# MAAV_Vehicle_12v0.net
KiCad netlist of a schematic drawn in EAGLE
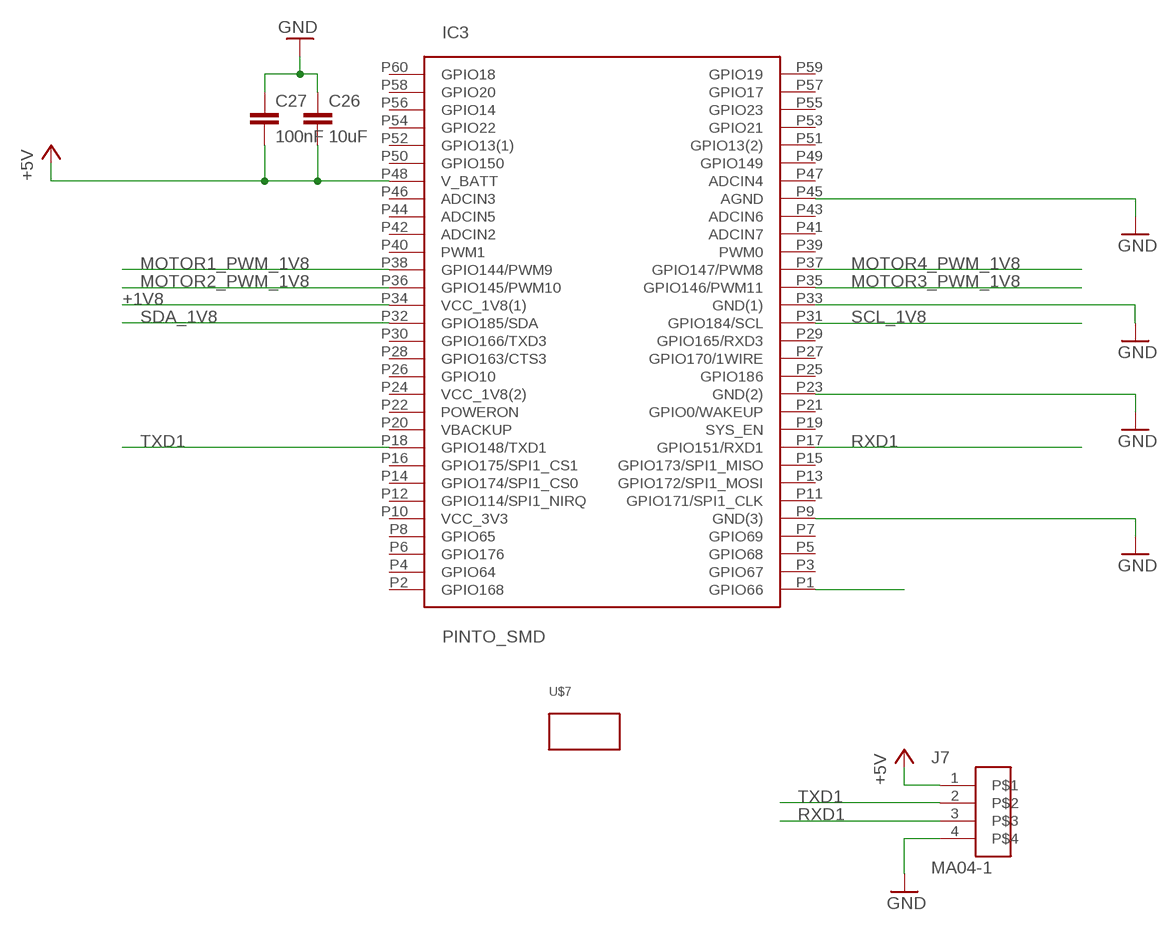
[diagram p0: schematic, sheet 1]
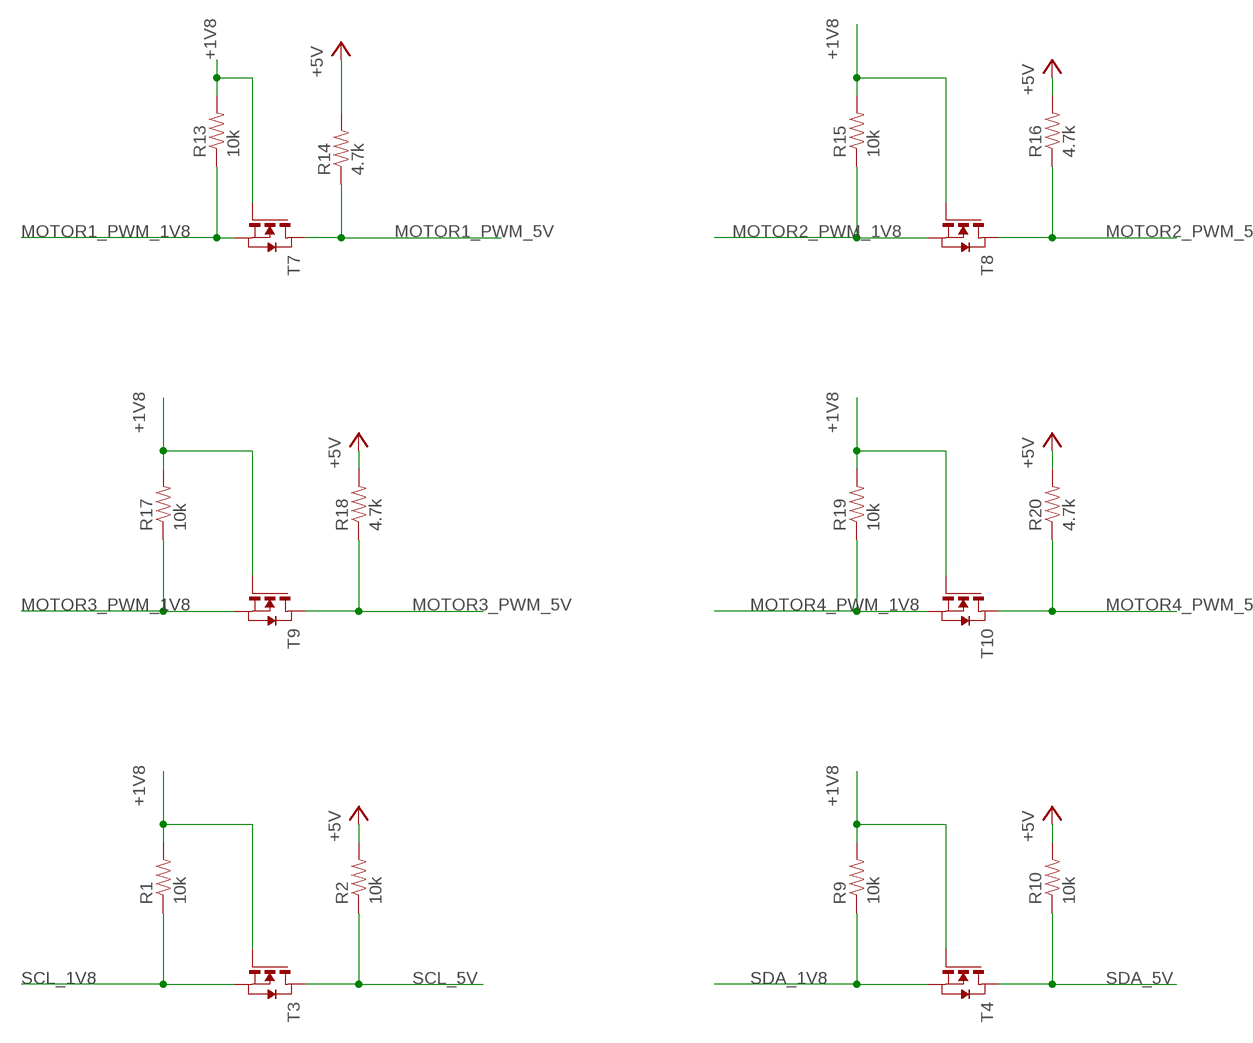
[diagram p1: schematic, sheet 2]
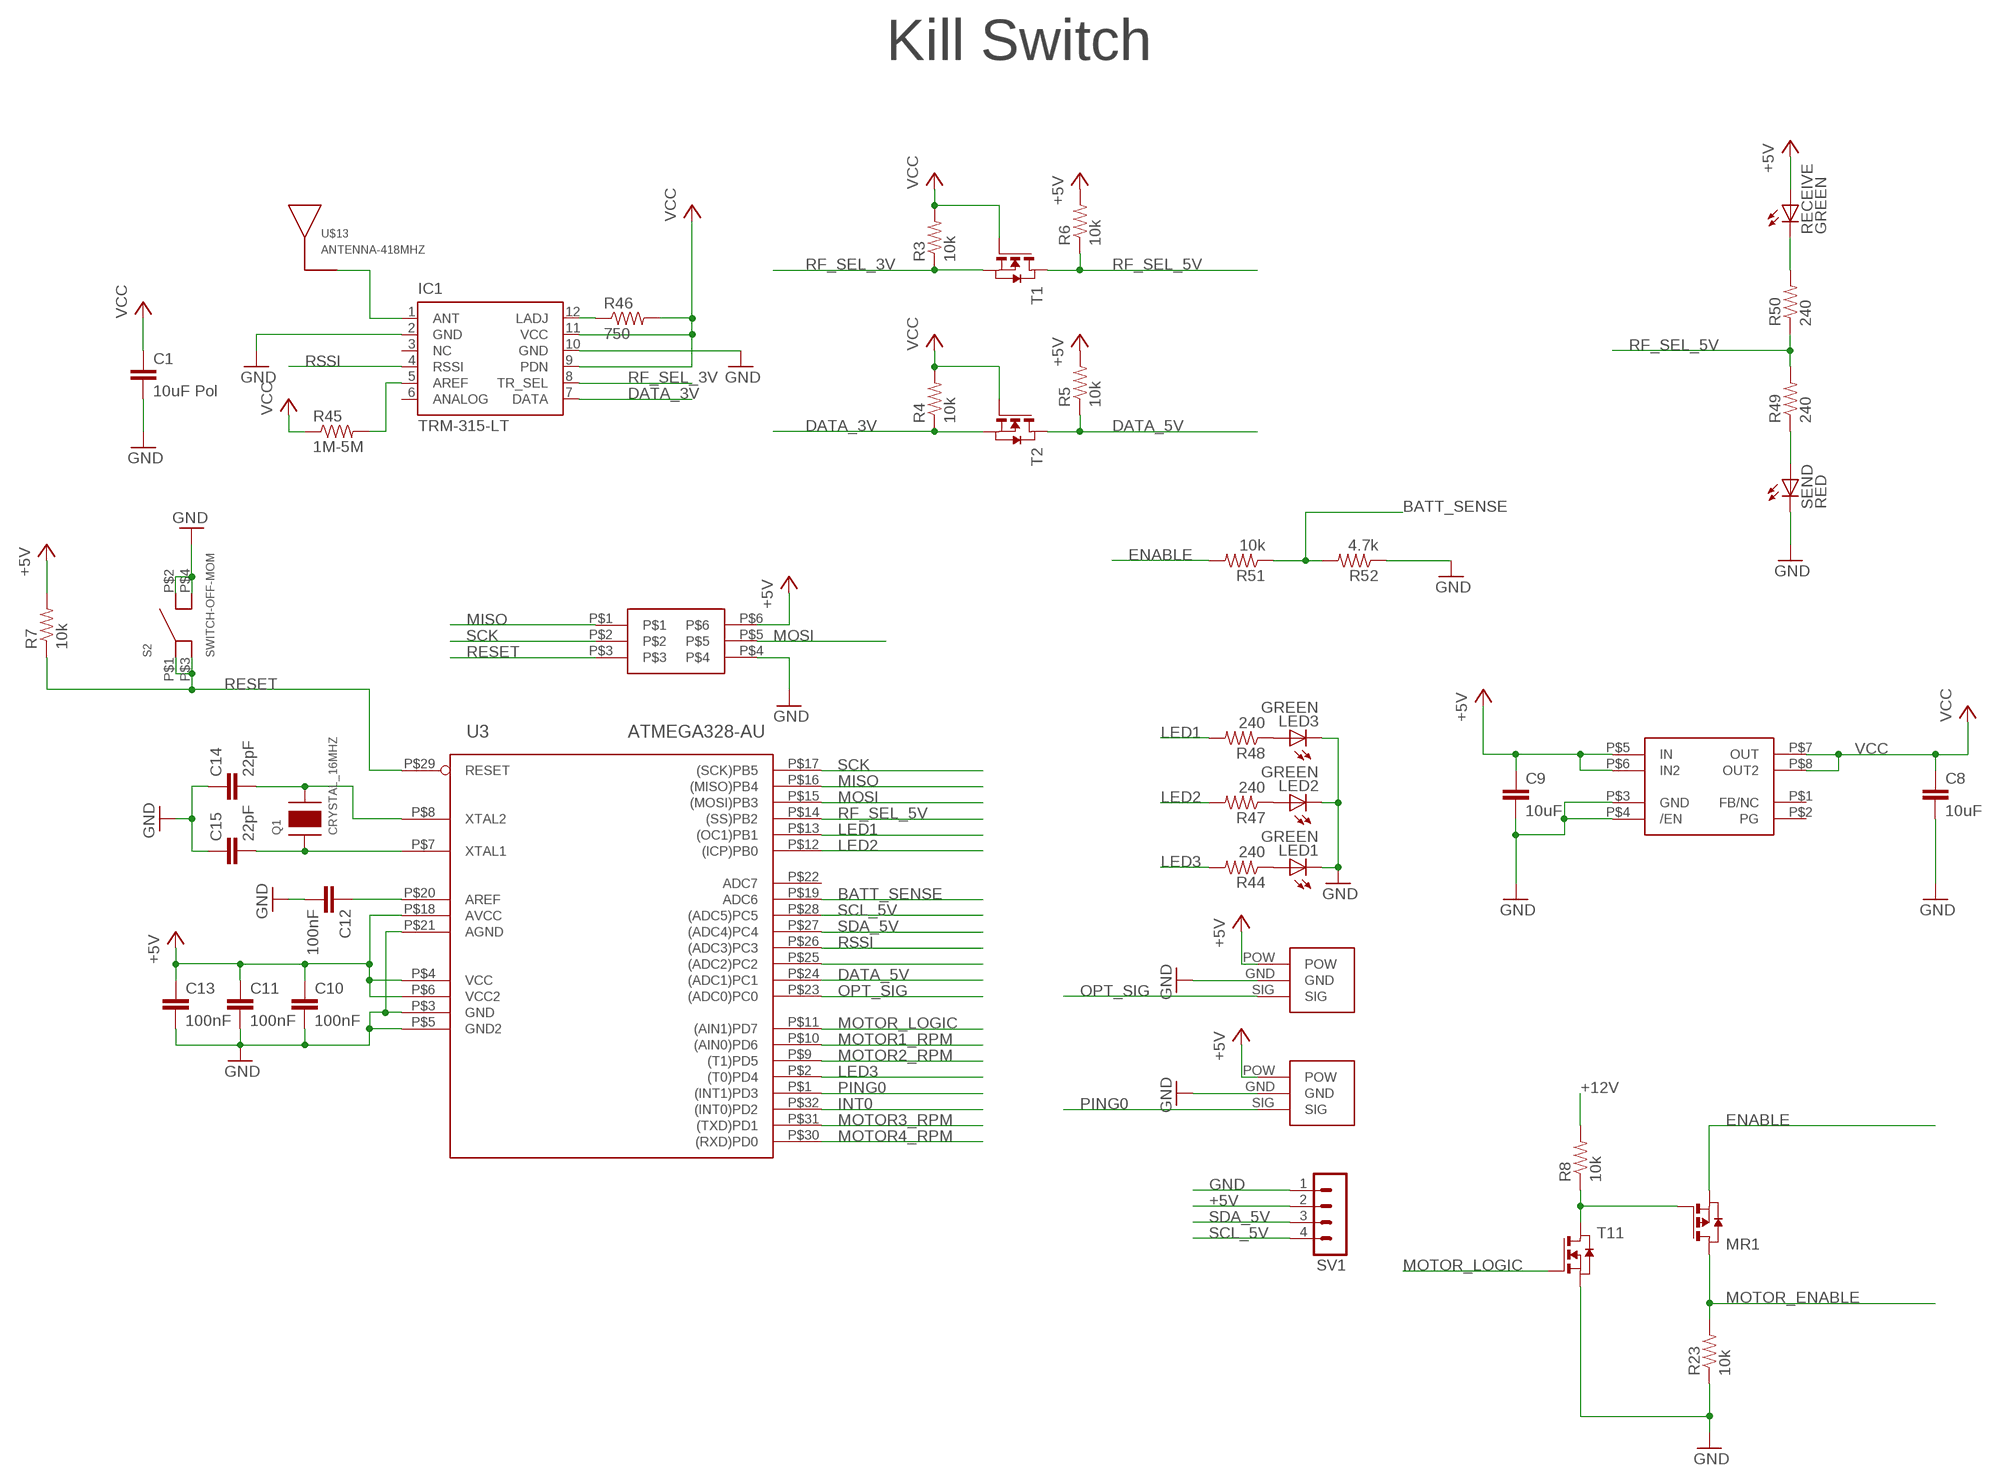
[diagram p2: schematic, sheet 3]
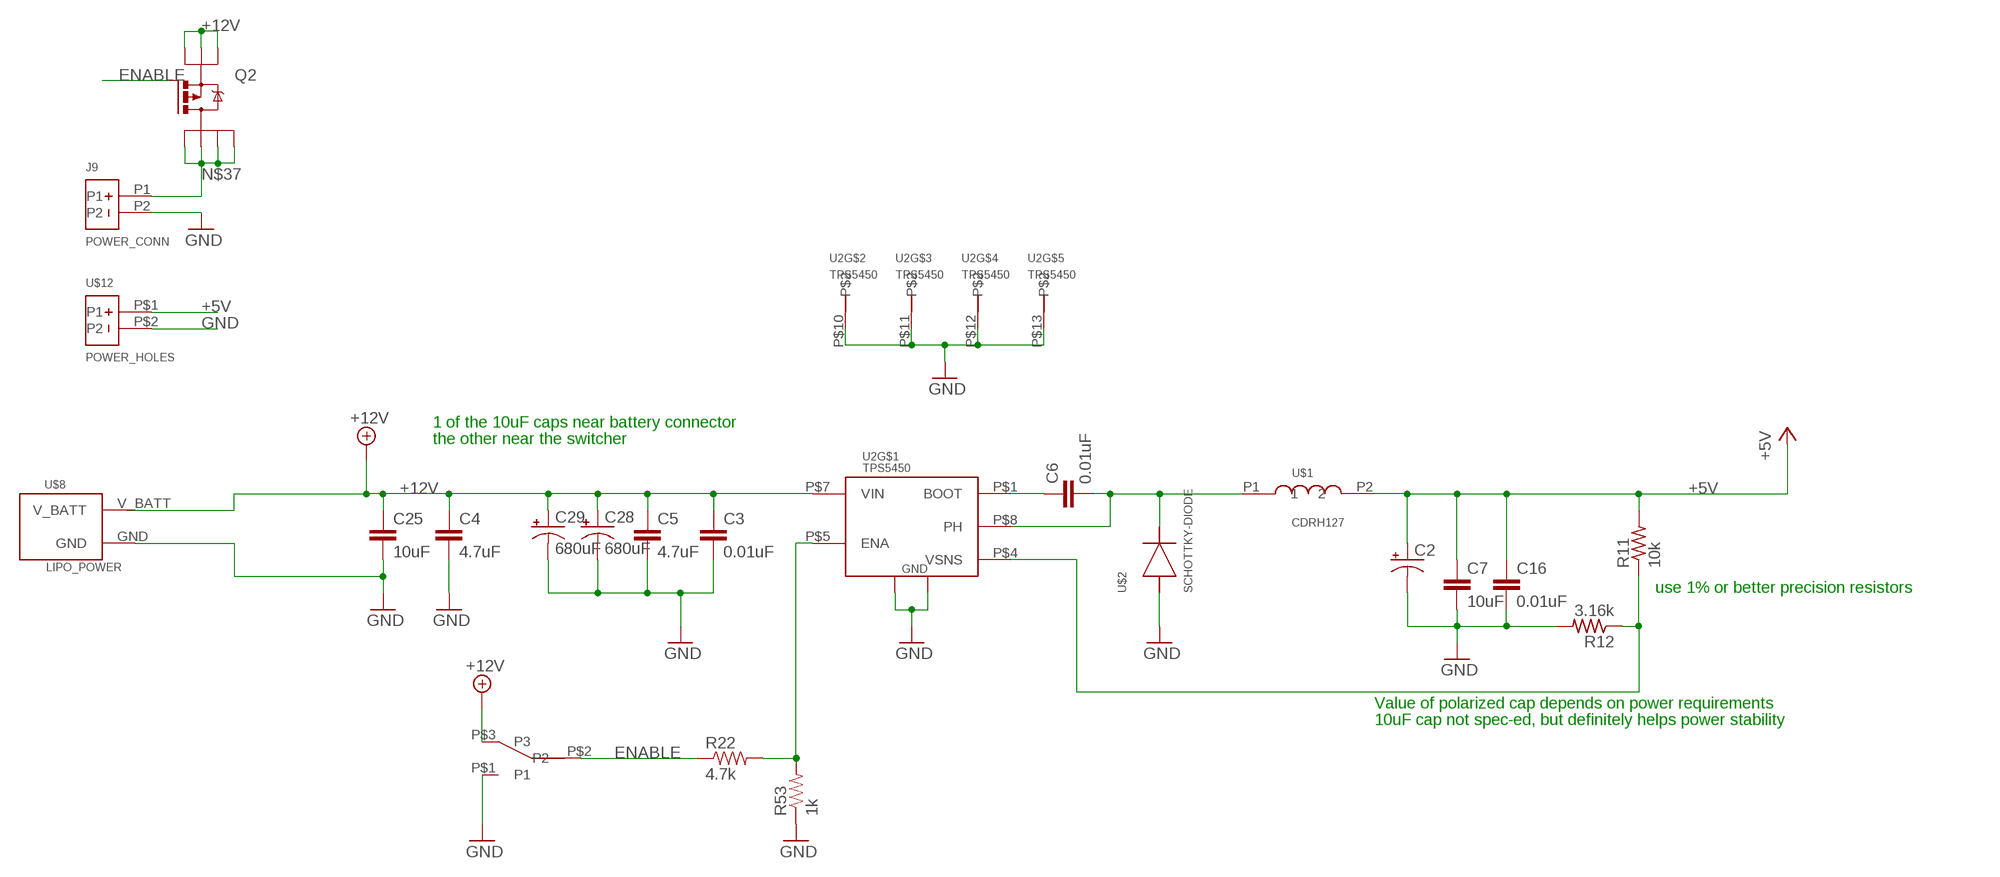
[diagram p3: schematic, sheet 4]
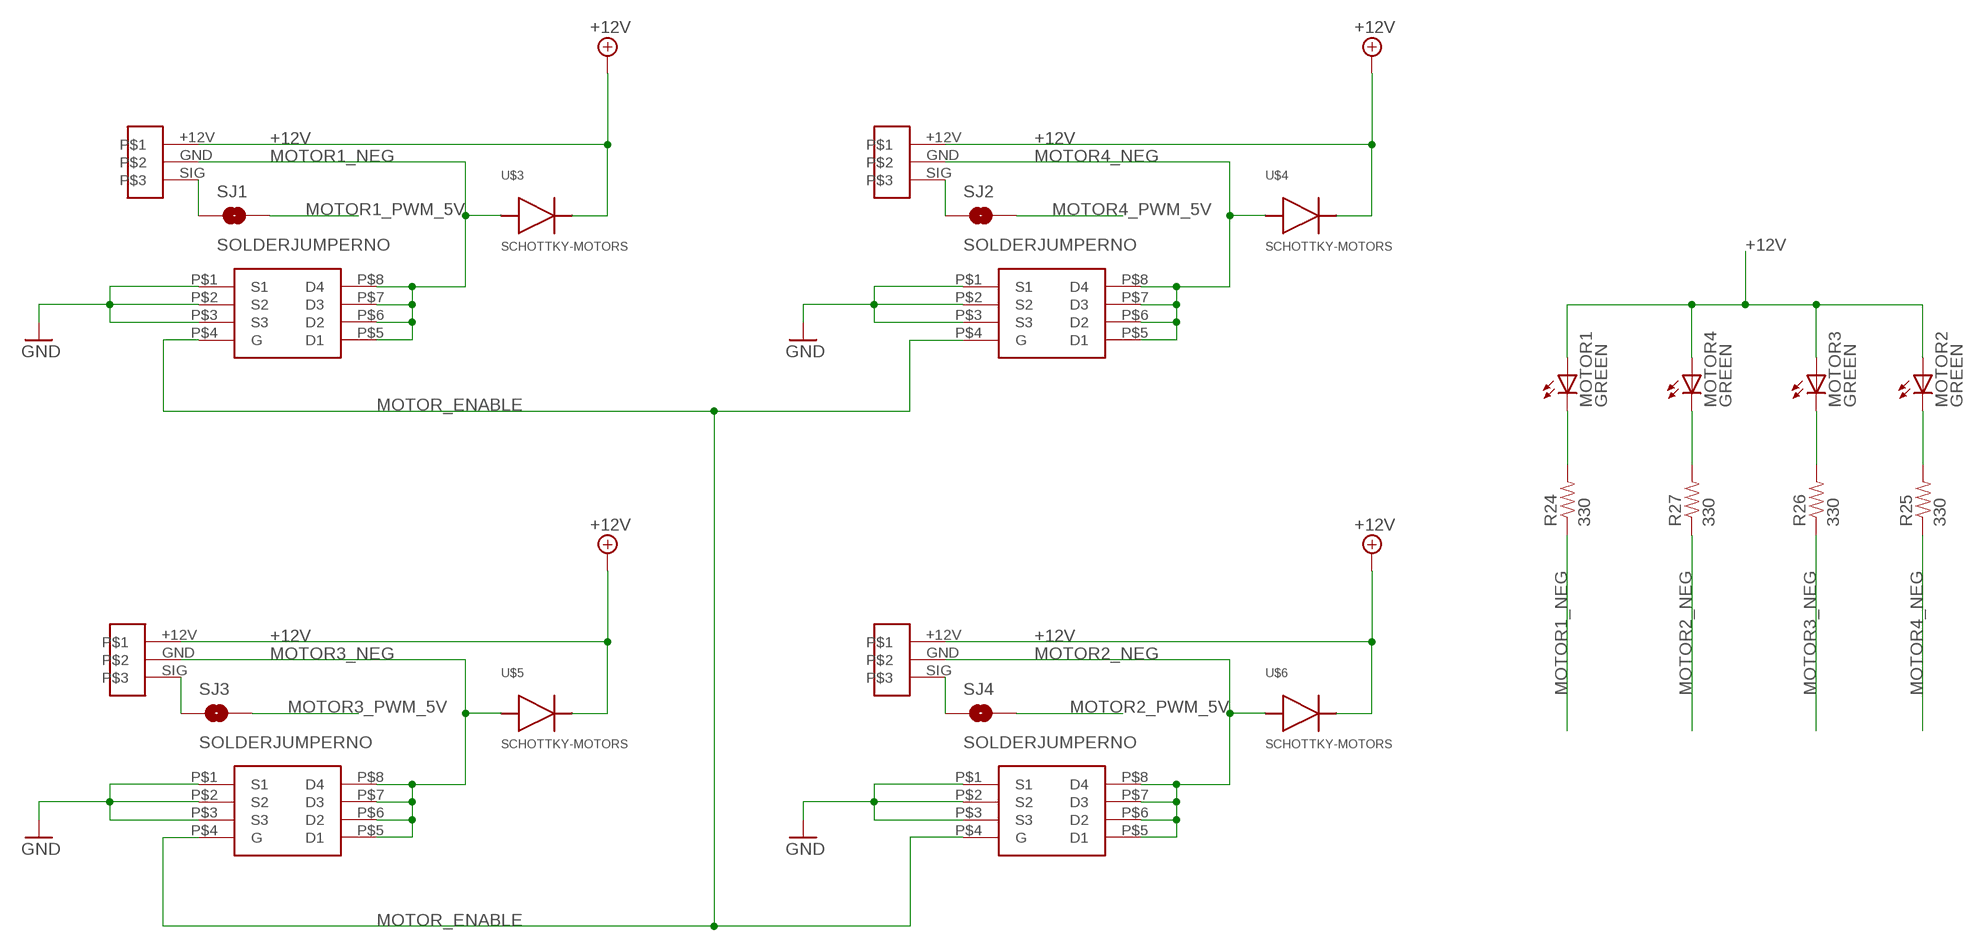
[diagram p4: schematic, sheet 5]
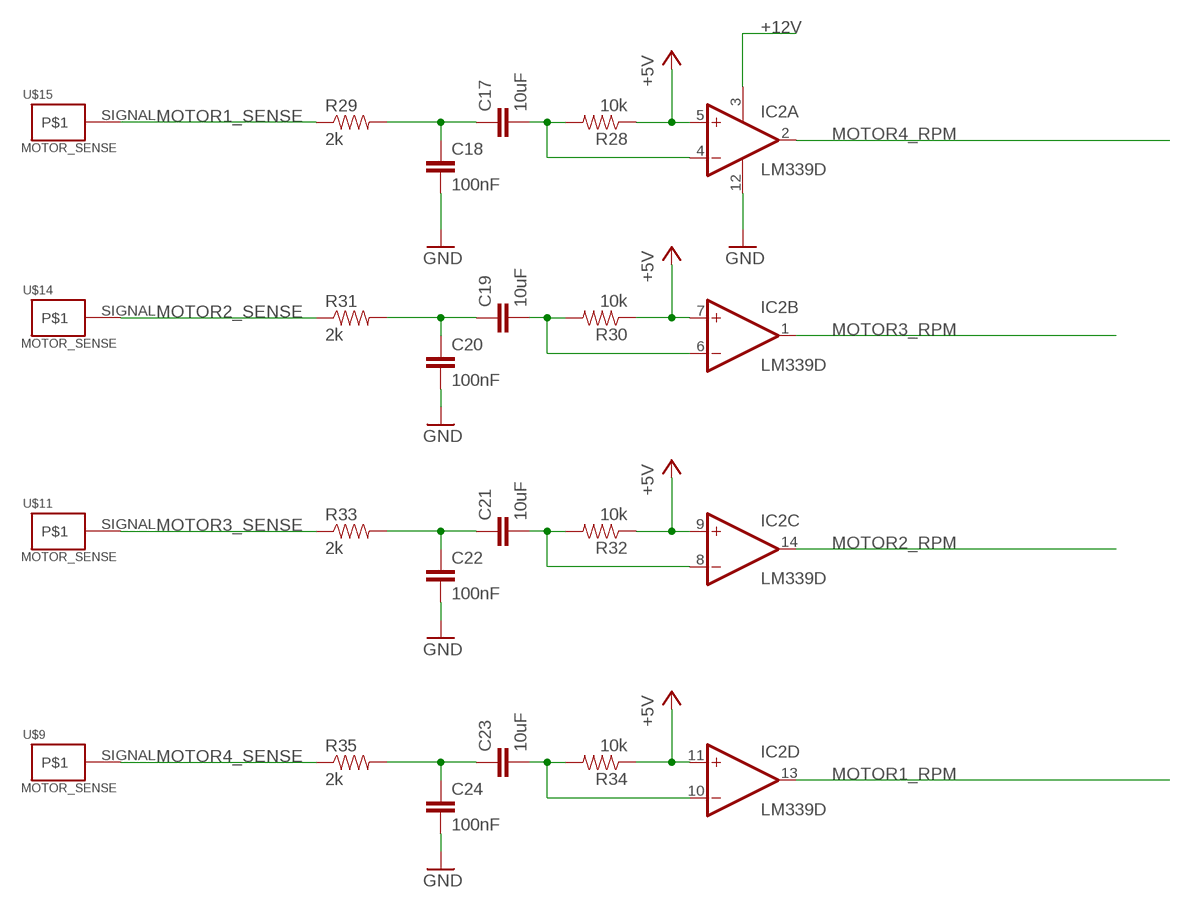
[diagram p5: schematic, sheet 6]
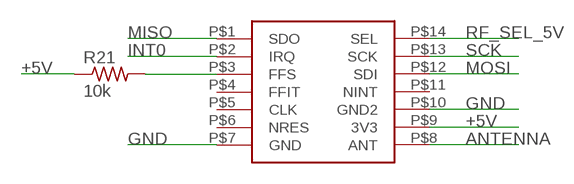
[diagram p6: schematic, sheet 7]

(export (version "E")
  (design (tool "Eeschema 10.0.6"))
  (components
    (comp (ref "C1")
      (value "10uF Pol")
      (footprint "eagle-import:0805")
      (libsource (lib "eagle-import") (part "CAP0805"))
    )
    (comp (ref "C8")
      (value "10uF")
      (footprint "eagle-import:0805")
      (libsource (lib "eagle-import") (part "CAP0805"))
    )
    (comp (ref "C9")
      (value "10uF")
      (footprint "eagle-import:0603-CAP")
      (libsource (lib "eagle-import") (part "CAP0603-CAP"))
    )
    (comp (ref "C10")
      (value "100nF")
      (footprint "eagle-import:0603-CAP")
      (libsource (lib "eagle-import") (part "CAP0603-CAP"))
    )
    (comp (ref "C11")
      (value "100nF")
      (footprint "eagle-import:0603-CAP")
      (libsource (lib "eagle-import") (part "CAP0603-CAP"))
    )
    (comp (ref "C12")
      (value "100nF")
      (footprint "eagle-import:0603-CAP")
      (libsource (lib "eagle-import") (part "CAP0603-CAP"))
    )
    (comp (ref "C13")
      (value "100nF")
      (footprint "eagle-import:0603-CAP")
      (libsource (lib "eagle-import") (part "CAP0603-CAP"))
    )
    (comp (ref "C14")
      (value "22pF")
      (footprint "eagle-import:0603-CAP")
      (libsource (lib "eagle-import") (part "CAP0603-CAP"))
    )
    (comp (ref "C15")
      (value "22pF")
      (footprint "eagle-import:0603-CAP")
      (libsource (lib "eagle-import") (part "CAP0603-CAP"))
    )
    (comp (ref "IC1")
      (value "TRM-315-LT")
      (footprint "eagle-import:TRM-XXX-LT")
      (libsource (lib "eagle-import") (part "TRM--LT315"))
    )
    (comp (ref "J1")
      (value "MA03-2")
      (footprint "eagle-import:MA03-2")
      (libsource (lib "eagle-import") (part "MA03-2"))
    )
    (comp (ref "LED1")
      (value "GREEN")
      (footprint "eagle-import:LED-0603")
      (libsource (lib "eagle-import") (part "LED0603"))
    )
    (comp (ref "LED2")
      (value "GREEN")
      (footprint "eagle-import:LED-0603")
      (libsource (lib "eagle-import") (part "LED0603"))
    )
    (comp (ref "LED3")
      (value "GREEN")
      (footprint "eagle-import:LED-0603")
      (libsource (lib "eagle-import") (part "LED0603"))
    )
    (comp (ref "MR1")
      (value "PMOSSOT23")
      (footprint "eagle-import:SOT-23")
      (libsource (lib "eagle-import") (part "PMOSSOT23"))
    )
    (comp (ref "Q1")
      (value "CRYSTAL_16MHZ")
      (footprint "eagle-import:CRYSTAL_16MHZ")
      (libsource (lib "eagle-import") (part "CRYSTAL_16MHZ"))
    )
    (comp (ref "R3")
      (value "10k")
      (footprint "eagle-import:0603-RES")
      (libsource (lib "eagle-import") (part "RESISTOR0603-RES"))
    )
    (comp (ref "R4")
      (value "10k")
      (footprint "eagle-import:0603-RES")
      (libsource (lib "eagle-import") (part "RESISTOR0603-RES"))
    )
    (comp (ref "R5")
      (value "10k")
      (footprint "eagle-import:0603-RES")
      (libsource (lib "eagle-import") (part "RESISTOR0603-RES"))
    )
    (comp (ref "R6")
      (value "10k")
      (footprint "eagle-import:0603-RES")
      (libsource (lib "eagle-import") (part "RESISTOR0603-RES"))
    )
    (comp (ref "R7")
      (value "10k")
      (footprint "eagle-import:0603-RES")
      (libsource (lib "eagle-import") (part "RESISTOR0603-RES"))
    )
    (comp (ref "R8")
      (value "10k")
      (footprint "eagle-import:0805")
      (libsource (lib "eagle-import") (part "RESISTOR0805-RES"))
    )
    (comp (ref "R23")
      (value "10k")
      (footprint "eagle-import:0805")
      (libsource (lib "eagle-import") (part "RESISTOR0805-RES"))
    )
    (comp (ref "R44")
      (value "240")
      (footprint "eagle-import:0603-RES")
      (libsource (lib "eagle-import") (part "RESISTOR0603-RES"))
    )
    (comp (ref "R45")
      (value "1M-5M")
      (footprint "eagle-import:0603-RES")
      (libsource (lib "eagle-import") (part "RESISTOR0603-RES"))
    )
    (comp (ref "R46")
      (value "750")
      (footprint "eagle-import:0603-RES")
      (libsource (lib "eagle-import") (part "RESISTOR0603-RES"))
    )
    (comp (ref "R47")
      (value "240")
      (footprint "eagle-import:0603-RES")
      (libsource (lib "eagle-import") (part "RESISTOR0603-RES"))
    )
    (comp (ref "R48")
      (value "240")
      (footprint "eagle-import:0603-RES")
      (libsource (lib "eagle-import") (part "RESISTOR0603-RES"))
    )
    (comp (ref "R49")
      (value "240")
      (footprint "eagle-import:0603-RES")
      (libsource (lib "eagle-import") (part "RESISTOR0603-RES"))
    )
    (comp (ref "R50")
      (value "240")
      (footprint "eagle-import:0603-RES")
      (libsource (lib "eagle-import") (part "RESISTOR0603-RES"))
    )
    (comp (ref "R51")
      (value "10k")
      (footprint "eagle-import:0603-RES")
      (libsource (lib "eagle-import") (part "RESISTOR0603-RES"))
    )
    (comp (ref "R52")
      (value "4.7k")
      (footprint "eagle-import:0603-RES")
      (libsource (lib "eagle-import") (part "RESISTOR0603-RES"))
    )
    (comp (ref "RECEIVE")
      (value "GREEN")
      (footprint "eagle-import:LED-0603")
      (libsource (lib "eagle-import") (part "LED0603"))
    )
    (comp (ref "S2")
      (value "SWITCH-OFF-MOM")
      (footprint "eagle-import:SWITCH-OFF-MOM")
      (libsource (lib "eagle-import") (part "SWITCH-OFF-MOM"))
    )
    (comp (ref "SEND")
      (value "RED")
      (footprint "eagle-import:LED-0603")
      (libsource (lib "eagle-import") (part "LED0603"))
    )
    (comp (ref "SV1")
      (value "MA04-1")
      (footprint "eagle-import:MA04-1")
      (libsource (lib "eagle-import") (part "con-lstb_MA04-1"))
    )
    (comp (ref "T1")
      (value "NMOSSOT23")
      (footprint "eagle-import:SOT-23")
      (libsource (lib "eagle-import") (part "NMOSSOT23"))
    )
    (comp (ref "T2")
      (value "NMOSSOT23")
      (footprint "eagle-import:SOT-23")
      (libsource (lib "eagle-import") (part "NMOSSOT23"))
    )
    (comp (ref "T11")
      (value "NMOSSOT23")
      (footprint "eagle-import:SOT-23")
      (libsource (lib "eagle-import") (part "NMOSSOT23"))
    )
    (comp (ref "U$10")
      (value "H3894-ND")
      (footprint "eagle-import:H3894-ND")
      (libsource (lib "eagle-import") (part "H3894-ND"))
    )
    (comp (ref "U$13")
      (value "ANTENNA-418MHZ")
      (footprint "eagle-import:ANTENNA-418MHZ")
      (libsource (lib "eagle-import") (part "ANTENNA-418MHZ"))
    )
    (comp (ref "U$16")
      (value "H3894-ND")
      (footprint "eagle-import:H3894-ND")
      (libsource (lib "eagle-import") (part "H3894-ND"))
    )
    (comp (ref "U3")
      (value "ATMEGA328-AU")
      (footprint "eagle-import:32-TQFP")
      (libsource (lib "eagle-import") (part "ATMEGA328-AU"))
    )
    (comp (ref "U4")
      (value "REG_3V_8SOIC")
      (footprint "eagle-import:8-SOIC")
      (libsource (lib "eagle-import") (part "REG_3V_8SOIC"))
    )
    (comp (ref "J2")
      (value "MOTOR_CONNTRU_HOLE")
      (footprint "eagle-import:MOTOR_CONN_THRU")
      (libsource (lib "eagle-import") (part "MOTOR_CONNTRU_HOLE"))
    )
    (comp (ref "J3")
      (value "MOTOR_CONNTRU_HOLE")
      (footprint "eagle-import:MOTOR_CONN_THRU")
      (libsource (lib "eagle-import") (part "MOTOR_CONNTRU_HOLE"))
    )
    (comp (ref "J4")
      (value "MOTOR_CONNTRU_HOLE")
      (footprint "eagle-import:MOTOR_CONN_THRU")
      (libsource (lib "eagle-import") (part "MOTOR_CONNTRU_HOLE"))
    )
    (comp (ref "J5")
      (value "MOTOR_CONNTRU_HOLE")
      (footprint "eagle-import:MOTOR_CONN_THRU")
      (libsource (lib "eagle-import") (part "MOTOR_CONNTRU_HOLE"))
    )
    (comp (ref "MOTOR1")
      (value "GREEN")
      (footprint "eagle-import:CHIPLED_0805")
      (libsource (lib "eagle-import") (part "LEDCHIPLED_0805"))
    )
    (comp (ref "MOTOR2")
      (value "GREEN")
      (footprint "eagle-import:CHIPLED_0805")
      (libsource (lib "eagle-import") (part "LEDCHIPLED_0805"))
    )
    (comp (ref "MOTOR3")
      (value "GREEN")
      (footprint "eagle-import:CHIPLED_0805")
      (libsource (lib "eagle-import") (part "LEDCHIPLED_0805"))
    )
    (comp (ref "MOTOR4")
      (value "GREEN")
      (footprint "eagle-import:CHIPLED_0805")
      (libsource (lib "eagle-import") (part "LEDCHIPLED_0805"))
    )
    (comp (ref "R24")
      (value "330")
      (footprint "eagle-import:0805")
      (libsource (lib "eagle-import") (part "RESISTOR0805-RES"))
    )
    (comp (ref "R25")
      (value "330")
      (footprint "eagle-import:0805")
      (libsource (lib "eagle-import") (part "RESISTOR0805-RES"))
    )
    (comp (ref "R26")
      (value "330")
      (footprint "eagle-import:0805")
      (libsource (lib "eagle-import") (part "RESISTOR0805-RES"))
    )
    (comp (ref "R27")
      (value "330")
      (footprint "eagle-import:0805")
      (libsource (lib "eagle-import") (part "RESISTOR0805-RES"))
    )
    (comp (ref "SJ1")
      (value "SOLDERJUMPERNO")
      (footprint "eagle-import:SJ_2S-NO")
      (libsource (lib "eagle-import") (part "SOLDERJUMPERNO"))
    )
    (comp (ref "SJ2")
      (value "SOLDERJUMPERNO")
      (footprint "eagle-import:SJ_2S-NO")
      (libsource (lib "eagle-import") (part "SOLDERJUMPERNO"))
    )
    (comp (ref "SJ3")
      (value "SOLDERJUMPERNO")
      (footprint "eagle-import:SJ_2S-NO")
      (libsource (lib "eagle-import") (part "SOLDERJUMPERNO"))
    )
    (comp (ref "SJ4")
      (value "SOLDERJUMPERNO")
      (footprint "eagle-import:SJ_2S-NO")
      (libsource (lib "eagle-import") (part "SOLDERJUMPERNO"))
    )
    (comp (ref "T5")
      (value "MOTOR_NFET")
      (footprint "eagle-import:8-SOIC")
      (libsource (lib "eagle-import") (part "MOTOR_NFET"))
    )
    (comp (ref "T6")
      (value "MOTOR_NFET")
      (footprint "eagle-import:8-SOIC")
      (libsource (lib "eagle-import") (part "MOTOR_NFET"))
    )
    (comp (ref "T12")
      (value "MOTOR_NFET")
      (footprint "eagle-import:8-SOIC")
      (libsource (lib "eagle-import") (part "MOTOR_NFET"))
    )
    (comp (ref "T13")
      (value "MOTOR_NFET")
      (footprint "eagle-import:8-SOIC")
      (libsource (lib "eagle-import") (part "MOTOR_NFET"))
    )
    (comp (ref "U$3")
      (value "SCHOTTKY-MOTORS")
      (footprint "eagle-import:DO-214AC,SMA")
      (libsource (lib "eagle-import") (part "SCHOTTKY-MOTORS"))
    )
    (comp (ref "U$4")
      (value "SCHOTTKY-MOTORS")
      (footprint "eagle-import:DO-214AC,SMA")
      (libsource (lib "eagle-import") (part "SCHOTTKY-MOTORS"))
    )
    (comp (ref "U$5")
      (value "SCHOTTKY-MOTORS")
      (footprint "eagle-import:DO-214AC,SMA")
      (libsource (lib "eagle-import") (part "SCHOTTKY-MOTORS"))
    )
    (comp (ref "U$6")
      (value "SCHOTTKY-MOTORS")
      (footprint "eagle-import:DO-214AC,SMA")
      (libsource (lib "eagle-import") (part "SCHOTTKY-MOTORS"))
    )
    (comp (ref "C17")
      (value "10uF")
      (footprint "eagle-import:0603-CAP")
      (libsource (lib "eagle-import") (part "CAP0603-CAP"))
    )
    (comp (ref "C18")
      (value "100nF")
      (footprint "eagle-import:0603-CAP")
      (libsource (lib "eagle-import") (part "CAP0603-CAP"))
    )
    (comp (ref "C19")
      (value "10uF")
      (footprint "eagle-import:0603-CAP")
      (libsource (lib "eagle-import") (part "CAP0603-CAP"))
    )
    (comp (ref "C20")
      (value "100nF")
      (footprint "eagle-import:0603-CAP")
      (libsource (lib "eagle-import") (part "CAP0603-CAP"))
    )
    (comp (ref "C21")
      (value "10uF")
      (footprint "eagle-import:0603-CAP")
      (libsource (lib "eagle-import") (part "CAP0603-CAP"))
    )
    (comp (ref "C22")
      (value "100nF")
      (footprint "eagle-import:0603-CAP")
      (libsource (lib "eagle-import") (part "CAP0603-CAP"))
    )
    (comp (ref "C23")
      (value "10uF")
      (footprint "eagle-import:0603-CAP")
      (libsource (lib "eagle-import") (part "CAP0603-CAP"))
    )
    (comp (ref "C24")
      (value "100nF")
      (footprint "eagle-import:0603-CAP")
      (libsource (lib "eagle-import") (part "CAP0603-CAP"))
    )
    (comp (ref "IC2")
      (value "LM339D")
      (footprint "eagle-import:SO14")
      (fields (field (name "DIGIKEY") "296-1013-1-ND"))
      (libsource (lib "eagle-import") (part "LM339D"))
    )
    (comp (ref "R28")
      (value "10k")
      (footprint "eagle-import:0603-RES")
      (libsource (lib "eagle-import") (part "RESISTOR0603-RES"))
    )
    (comp (ref "R29")
      (value "2k")
      (footprint "eagle-import:0603-RES")
      (libsource (lib "eagle-import") (part "RESISTOR0603-RES"))
    )
    (comp (ref "R30")
      (value "10k")
      (footprint "eagle-import:0603-RES")
      (libsource (lib "eagle-import") (part "RESISTOR0603-RES"))
    )
    (comp (ref "R31")
      (value "2k")
      (footprint "eagle-import:0603-RES")
      (libsource (lib "eagle-import") (part "RESISTOR0603-RES"))
    )
    (comp (ref "R32")
      (value "10k")
      (footprint "eagle-import:0603-RES")
      (libsource (lib "eagle-import") (part "RESISTOR0603-RES"))
    )
    (comp (ref "R33")
      (value "2k")
      (footprint "eagle-import:0603-RES")
      (libsource (lib "eagle-import") (part "RESISTOR0603-RES"))
    )
    (comp (ref "R34")
      (value "10k")
      (footprint "eagle-import:0603-RES")
      (libsource (lib "eagle-import") (part "RESISTOR0603-RES"))
    )
    (comp (ref "R35")
      (value "2k")
      (footprint "eagle-import:0603-RES")
      (libsource (lib "eagle-import") (part "RESISTOR0603-RES"))
    )
    (comp (ref "U$9")
      (value "MOTOR_SENSE")
      (footprint "eagle-import:MOTOR_SENSE")
      (libsource (lib "eagle-import") (part "MOTOR_SENSE"))
    )
    (comp (ref "U$11")
      (value "MOTOR_SENSE")
      (footprint "eagle-import:MOTOR_SENSE")
      (libsource (lib "eagle-import") (part "MOTOR_SENSE"))
    )
    (comp (ref "U$14")
      (value "MOTOR_SENSE")
      (footprint "eagle-import:MOTOR_SENSE")
      (libsource (lib "eagle-import") (part "MOTOR_SENSE"))
    )
    (comp (ref "U$15")
      (value "MOTOR_SENSE")
      (footprint "eagle-import:MOTOR_SENSE")
      (libsource (lib "eagle-import") (part "MOTOR_SENSE"))
    )
    (comp (ref "R21")
      (value "10k")
      (footprint "eagle-import:R0603")
      (libsource (lib "eagle-import") (part "R-US_R0603"))
    )
    (comp (ref "U$17")
      (value "RF12")
      (footprint "eagle-import:RF12")
      (libsource (lib "eagle-import") (part "RF12"))
    )
    (comp (ref "R1")
      (value "10k")
      (footprint "eagle-import:0603-RES")
      (libsource (lib "eagle-import") (part "RESISTOR0603-RES"))
    )
    (comp (ref "R2")
      (value "10k")
      (footprint "eagle-import:0603-RES")
      (libsource (lib "eagle-import") (part "RESISTOR0603-RES"))
    )
    (comp (ref "R9")
      (value "10k")
      (footprint "eagle-import:0603-RES")
      (libsource (lib "eagle-import") (part "RESISTOR0603-RES"))
    )
    (comp (ref "R10")
      (value "10k")
      (footprint "eagle-import:0603-RES")
      (libsource (lib "eagle-import") (part "RESISTOR0603-RES"))
    )
    (comp (ref "R13")
      (value "10k")
      (footprint "eagle-import:0603-RES")
      (libsource (lib "eagle-import") (part "RESISTOR0603-RES"))
    )
    (comp (ref "R14")
      (value "4.7k")
      (footprint "eagle-import:0603-RES")
      (libsource (lib "eagle-import") (part "RESISTOR0603-RES"))
    )
    (comp (ref "R15")
      (value "10k")
      (footprint "eagle-import:0603-RES")
      (libsource (lib "eagle-import") (part "RESISTOR0603-RES"))
    )
    (comp (ref "R16")
      (value "4.7k")
      (footprint "eagle-import:0603-RES")
      (libsource (lib "eagle-import") (part "RESISTOR0603-RES"))
    )
    (comp (ref "R17")
      (value "10k")
      (footprint "eagle-import:0603-RES")
      (libsource (lib "eagle-import") (part "RESISTOR0603-RES"))
    )
    (comp (ref "R18")
      (value "4.7k")
      (footprint "eagle-import:0603-RES")
      (libsource (lib "eagle-import") (part "RESISTOR0603-RES"))
    )
    (comp (ref "R19")
      (value "10k")
      (footprint "eagle-import:0603-RES")
      (libsource (lib "eagle-import") (part "RESISTOR0603-RES"))
    )
    (comp (ref "R20")
      (value "4.7k")
      (footprint "eagle-import:0603-RES")
      (libsource (lib "eagle-import") (part "RESISTOR0603-RES"))
    )
    (comp (ref "T3")
      (value "NMOSSOT23")
      (footprint "eagle-import:SOT-23")
      (libsource (lib "eagle-import") (part "NMOSSOT23"))
    )
    (comp (ref "T4")
      (value "NMOSSOT23")
      (footprint "eagle-import:SOT-23")
      (libsource (lib "eagle-import") (part "NMOSSOT23"))
    )
    (comp (ref "T7")
      (value "NMOSSOT23")
      (footprint "eagle-import:SOT-23")
      (libsource (lib "eagle-import") (part "NMOSSOT23"))
    )
    (comp (ref "T8")
      (value "NMOSSOT23")
      (footprint "eagle-import:SOT-23")
      (libsource (lib "eagle-import") (part "NMOSSOT23"))
    )
    (comp (ref "T9")
      (value "NMOSSOT23")
      (footprint "eagle-import:SOT-23")
      (libsource (lib "eagle-import") (part "NMOSSOT23"))
    )
    (comp (ref "T10")
      (value "NMOSSOT23")
      (footprint "eagle-import:SOT-23")
      (libsource (lib "eagle-import") (part "NMOSSOT23"))
    )
    (comp (ref "C26")
      (value "10uF")
      (footprint "eagle-import:0603-CAP")
      (libsource (lib "eagle-import") (part "CAP0603-CAP"))
    )
    (comp (ref "C27")
      (value "100nF")
      (footprint "eagle-import:0603-CAP")
      (libsource (lib "eagle-import") (part "CAP0603-CAP"))
    )
    (comp (ref "IC3")
      (value "PINTO_SMD")
      (footprint "eagle-import:PINTO_SMD")
      (libsource (lib "eagle-import") (part "PINTO_SMD"))
    )
    (comp (ref "J7")
      (value "MA04-1")
      (footprint "eagle-import:455-1751-1-ND")
      (libsource (lib "eagle-import") (part "MA04-1"))
    )
    (comp (ref "U$7")
      (value "IMU")
      (footprint "eagle-import:IMU")
      (libsource (lib "eagle-import") (part "IMU"))
    )
    (comp (ref "C2")
      (value "CAP_POL")
      (footprint "eagle-import:2917")
      (libsource (lib "eagle-import") (part "CAP_POL"))
    )
    (comp (ref "C3")
      (value "0.01uF")
      (footprint "eagle-import:C1210")
      (libsource (lib "eagle-import") (part "C-EUC1210"))
    )
    (comp (ref "C4")
      (value "4.7uF")
      (footprint "eagle-import:C1210")
      (libsource (lib "eagle-import") (part "C-EUC1210"))
    )
    (comp (ref "C5")
      (value "4.7uF")
      (footprint "eagle-import:C1210")
      (libsource (lib "eagle-import") (part "C-EUC1210"))
    )
    (comp (ref "C6")
      (value "0.01uF")
      (footprint "eagle-import:C1210")
      (libsource (lib "eagle-import") (part "C-EUC1210"))
    )
    (comp (ref "C7")
      (value "10uF")
      (footprint "eagle-import:C1210")
      (libsource (lib "eagle-import") (part "C-EUC1210"))
    )
    (comp (ref "C16")
      (value "0.01uF")
      (footprint "eagle-import:C1210")
      (libsource (lib "eagle-import") (part "C-EUC1210"))
    )
    (comp (ref "C25")
      (value "10uF")
      (footprint "eagle-import:C1210")
      (libsource (lib "eagle-import") (part "C-EUC1210"))
    )
    (comp (ref "C28")
      (value "680uF")
      (footprint "eagle-import:EH22-9")
      (libsource (lib "eagle-import") (part "CPOL-USE22-9AXIAL"))
    )
    (comp (ref "C29")
      (value "680uF")
      (footprint "eagle-import:EH22-9")
      (libsource (lib "eagle-import") (part "CPOL-USE22-9AXIAL"))
    )
    (comp (ref "J9")
      (value "POWER_CONN")
      (footprint "eagle-import:POWER_CONN")
      (libsource (lib "eagle-import") (part "POWER_CONN"))
    )
    (comp (ref "Q2")
      (value "P-MOSFET-SO8")
      (footprint "eagle-import:SO-08")
      (libsource (lib "eagle-import") (part "P-MOSFET-SO8"))
    )
    (comp (ref "R11")
      (value "10k")
      (footprint "eagle-import:R0603")
      (libsource (lib "eagle-import") (part "resistor_R-US_R0603"))
    )
    (comp (ref "R12")
      (value "3.16k")
      (footprint "eagle-import:R0603")
      (libsource (lib "eagle-import") (part "resistor_R-US_R0603"))
    )
    (comp (ref "R22")
      (value "4.7k")
      (footprint "eagle-import:0805")
      (libsource (lib "eagle-import") (part "RESISTOR0805-RES"))
    )
    (comp (ref "R53")
      (value "1k")
      (footprint "eagle-import:0805")
      (libsource (lib "eagle-import") (part "RESISTOR0805-RES"))
    )
    (comp (ref "S1")
      (value "SWITCH-ON-ON")
      (footprint "eagle-import:SWITCH-ON-ON")
      (libsource (lib "eagle-import") (part "SWITCH-ON-ON"))
    )
    (comp (ref "U$1")
      (value "CDRH127")
      (footprint "eagle-import:CDRH127")
      (libsource (lib "eagle-import") (part "CDRH127"))
    )
    (comp (ref "U$2")
      (value "SCHOTTKY-DIODE")
      (footprint "eagle-import:DO-214AB,SMC")
      (libsource (lib "eagle-import") (part "SCHOTTKY-DIODE"))
    )
    (comp (ref "U$8")
      (value "LIPO_POWER")
      (footprint "eagle-import:LIPO_POWER")
      (libsource (lib "eagle-import") (part "LIPO_POWER"))
    )
    (comp (ref "U$12")
      (value "POWER_HOLES")
      (footprint "eagle-import:POWER_HOLES")
      (libsource (lib "eagle-import") (part "POWER_HOLES"))
    )
    (comp (ref "U2")
      (value "TPS5450")
      (footprint "eagle-import:TPS5450")
      (libsource (lib "eagle-import") (part "TPS5450"))
    )
  )
  (nets
    (net (code "1") (name "+1V8") (class "Default")
      (node (ref "IC3") (pin "P34") (pinfunction "VCC_1V8(1)_P34") (pintype "bidirectional"))
      (node (ref "R1") (pin "2") (pinfunction "2_2") (pintype "passive"))
      (node (ref "R13") (pin "2") (pinfunction "2_2") (pintype "passive"))
      (node (ref "R15") (pin "2") (pinfunction "2_2") (pintype "passive"))
      (node (ref "R17") (pin "2") (pinfunction "2_2") (pintype "passive"))
      (node (ref "R19") (pin "2") (pinfunction "2_2") (pintype "passive"))
      (node (ref "R9") (pin "2") (pinfunction "2_2") (pintype "passive"))
      (node (ref "T10") (pin "3") (pinfunction "G_3") (pintype "passive"))
      (node (ref "T3") (pin "3") (pinfunction "G_3") (pintype "passive"))
      (node (ref "T4") (pin "3") (pinfunction "G_3") (pintype "passive"))
      (node (ref "T7") (pin "3") (pinfunction "G_3") (pintype "passive"))
      (node (ref "T8") (pin "3") (pinfunction "G_3") (pintype "passive"))
      (node (ref "T9") (pin "3") (pinfunction "G_3") (pintype "passive"))
    )
    (net (code "2") (name "+5V") (class "Default")
      (node (ref "C10") (pin "1") (pinfunction "1_1") (pintype "passive"))
      (node (ref "C11") (pin "1") (pinfunction "1_1") (pintype "passive"))
      (node (ref "C13") (pin "1") (pinfunction "1_1") (pintype "passive"))
      (node (ref "C16") (pin "1") (pinfunction "1_1") (pintype "passive"))
      (node (ref "C2") (pin "2") (pinfunction "+_2") (pintype "passive"))
      (node (ref "C26") (pin "2") (pinfunction "2_2") (pintype "passive"))
      (node (ref "C27") (pin "2") (pinfunction "2_2") (pintype "passive"))
      (node (ref "C7") (pin "1") (pinfunction "1_1") (pintype "passive"))
      (node (ref "C9") (pin "1") (pinfunction "1_1") (pintype "passive"))
      (node (ref "IC2") (pin "11") (pinfunction "+IN_11") (pintype "input"))
      (node (ref "IC2") (pin "5") (pinfunction "+IN_5") (pintype "input"))
      (node (ref "IC2") (pin "7") (pinfunction "+IN_7") (pintype "input"))
      (node (ref "IC2") (pin "9") (pinfunction "+IN_9") (pintype "input"))
      (node (ref "IC3") (pin "P48") (pinfunction "V_BATT_P48") (pintype "bidirectional"))
      (node (ref "J1") (pin "P$6") (pinfunction "P$6_P$6") (pintype "bidirectional"))
      (node (ref "J7") (pin "1") (pinfunction "P$1_1") (pintype "bidirectional"))
      (node (ref "R10") (pin "2") (pinfunction "2_2") (pintype "passive"))
      (node (ref "R11") (pin "2") (pinfunction "2_2") (pintype "passive"))
      (node (ref "R14") (pin "2") (pinfunction "2_2") (pintype "passive"))
      (node (ref "R16") (pin "2") (pinfunction "2_2") (pintype "passive"))
      (node (ref "R18") (pin "2") (pinfunction "2_2") (pintype "passive"))
      (node (ref "R2") (pin "2") (pinfunction "2_2") (pintype "passive"))
      (node (ref "R20") (pin "2") (pinfunction "2_2") (pintype "passive"))
      (node (ref "R21") (pin "1") (pinfunction "1_1") (pintype "passive"))
      (node (ref "R28") (pin "1") (pinfunction "1_1") (pintype "passive"))
      (node (ref "R30") (pin "1") (pinfunction "1_1") (pintype "passive"))
      (node (ref "R32") (pin "1") (pinfunction "1_1") (pintype "passive"))
      (node (ref "R34") (pin "1") (pinfunction "1_1") (pintype "passive"))
      (node (ref "R5") (pin "2") (pinfunction "2_2") (pintype "passive"))
      (node (ref "R6") (pin "2") (pinfunction "2_2") (pintype "passive"))
      (node (ref "R7") (pin "2") (pinfunction "2_2") (pintype "passive"))
      (node (ref "RECEIVE") (pin "A") (pinfunction "A_A") (pintype "passive"))
      (node (ref "SV1") (pin "2") (pinfunction "2_2") (pintype "passive"))
      (node (ref "U$1") (pin "P2") (pinfunction "2_P2") (pintype "bidirectional"))
      (node (ref "U$10") (pin "POW") (pinfunction "POW_POW") (pintype "bidirectional"))
      (node (ref "U$12") (pin "P$1") (pinfunction "P1_P$1") (pintype "bidirectional"))
      (node (ref "U$16") (pin "POW") (pinfunction "POW_POW") (pintype "bidirectional"))
      (node (ref "U$17") (pin "P$9") (pinfunction "3V3_P$9") (pintype "bidirectional"))
      (node (ref "U3") (pin "P$18") (pinfunction "AVCC_P$18") (pintype "bidirectional"))
      (node (ref "U3") (pin "P$4") (pinfunction "VCC_P$4") (pintype "bidirectional"))
      (node (ref "U3") (pin "P$6") (pinfunction "VCC2_P$6") (pintype "bidirectional"))
      (node (ref "U4") (pin "P$5") (pinfunction "IN_P$5") (pintype "bidirectional"))
      (node (ref "U4") (pin "P$6") (pinfunction "IN2_P$6") (pintype "bidirectional"))
    )
    (net (code "3") (name "+12V") (class "Default")
      (node (ref "C25") (pin "1") (pinfunction "1_1") (pintype "passive"))
      (node (ref "C28") (pin "+") (pinfunction "+_+") (pintype "passive"))
      (node (ref "C29") (pin "+") (pinfunction "+_+") (pintype "passive"))
      (node (ref "C3") (pin "1") (pinfunction "1_1") (pintype "passive"))
      (node (ref "C4") (pin "1") (pinfunction "1_1") (pintype "passive"))
      (node (ref "C5") (pin "1") (pinfunction "1_1") (pintype "passive"))
      (node (ref "IC2") (pin "3") (pinfunction "V+_3") (pintype "power_in"))
      (node (ref "J2") (pin "+12V") (pinfunction "P$1_+12V") (pintype "bidirectional"))
      (node (ref "J3") (pin "+12V") (pinfunction "P$1_+12V") (pintype "bidirectional"))
      (node (ref "J4") (pin "+12V") (pinfunction "P$1_+12V") (pintype "bidirectional"))
      (node (ref "J5") (pin "+12V") (pinfunction "P$1_+12V") (pintype "bidirectional"))
      (node (ref "MOTOR1") (pin "A") (pinfunction "A_A") (pintype "passive"))
      (node (ref "MOTOR2") (pin "A") (pinfunction "A_A") (pintype "passive"))
      (node (ref "MOTOR3") (pin "A") (pinfunction "A_A") (pintype "passive"))
      (node (ref "MOTOR4") (pin "A") (pinfunction "A_A") (pintype "passive"))
      (node (ref "Q2") (pin "1") (pinfunction "S_1") (pintype "passive"))
      (node (ref "Q2") (pin "2") (pinfunction "S_2") (pintype "passive"))
      (node (ref "Q2") (pin "3") (pinfunction "S_3") (pintype "passive"))
      (node (ref "R8") (pin "2") (pinfunction "2_2") (pintype "passive"))
      (node (ref "S1") (pin "P$3") (pinfunction "P3_P$3") (pintype "bidirectional"))
      (node (ref "U$3") (pin "P$2") (pinfunction "P$2_P$2") (pintype "bidirectional"))
      (node (ref "U$4") (pin "P$2") (pinfunction "P$2_P$2") (pintype "bidirectional"))
      (node (ref "U$5") (pin "P$2") (pinfunction "P$2_P$2") (pintype "bidirectional"))
      (node (ref "U$6") (pin "P$2") (pinfunction "P$2_P$2") (pintype "bidirectional"))
      (node (ref "U$8") (pin "V_BATT") (pinfunction "V_BATT_V_BATT") (pintype "bidirectional"))
      (node (ref "U2") (pin "P$7") (pinfunction "VIN_P$7") (pintype "bidirectional"))
    )
    (net (code "4") (name "ANTENNA") (class "Default")
      (node (ref "IC1") (pin "1") (pinfunction "ANT_1") (pintype "passive"))
      (node (ref "U$13") (pin "P$1") (pinfunction "P$1_P$1") (pintype "bidirectional"))
      (node (ref "U$17") (pin "P$8") (pinfunction "ANT_P$8") (pintype "bidirectional"))
    )
    (net (code "5") (name "BATT_SENSE") (class "Default")
      (node (ref "R51") (pin "1") (pinfunction "1_1") (pintype "passive"))
      (node (ref "R52") (pin "2") (pinfunction "2_2") (pintype "passive"))
      (node (ref "U3") (pin "P$19") (pinfunction "ADC6_P$19") (pintype "bidirectional"))
    )
    (net (code "6") (name "DATA_3V") (class "Default")
      (node (ref "IC1") (pin "7") (pinfunction "DATA_7") (pintype "output"))
      (node (ref "R4") (pin "1") (pinfunction "1_1") (pintype "passive"))
      (node (ref "T2") (pin "2") (pinfunction "S_2") (pintype "passive"))
    )
    (net (code "7") (name "DATA_5V") (class "Default")
      (node (ref "R5") (pin "1") (pinfunction "1_1") (pintype "passive"))
      (node (ref "T2") (pin "1") (pinfunction "D_1") (pintype "passive"))
      (node (ref "U3") (pin "P$24") (pinfunction "(ADC1)PC1_P$24") (pintype "bidirectional"))
    )
    (net (code "8") (name "ENABLE") (class "Default")
      (node (ref "MR1") (pin "2") (pinfunction "S_2") (pintype "passive"))
      (node (ref "Q2") (pin "4") (pinfunction "G_4") (pintype "passive"))
      (node (ref "R22") (pin "1") (pinfunction "1_1") (pintype "passive"))
      (node (ref "R51") (pin "2") (pinfunction "2_2") (pintype "passive"))
      (node (ref "S1") (pin "P$2") (pinfunction "P2_P$2") (pintype "bidirectional"))
    )
    (net (code "9") (name "GND") (class "Default")
      (node (ref "C1") (pin "2") (pinfunction "2_2") (pintype "passive"))
      (node (ref "C10") (pin "2") (pinfunction "2_2") (pintype "passive"))
      (node (ref "C11") (pin "2") (pinfunction "2_2") (pintype "passive"))
      (node (ref "C12") (pin "2") (pinfunction "2_2") (pintype "passive"))
      (node (ref "C13") (pin "2") (pinfunction "2_2") (pintype "passive"))
      (node (ref "C14") (pin "1") (pinfunction "1_1") (pintype "passive"))
      (node (ref "C15") (pin "1") (pinfunction "1_1") (pintype "passive"))
      (node (ref "C16") (pin "2") (pinfunction "2_2") (pintype "passive"))
      (node (ref "C18") (pin "2") (pinfunction "2_2") (pintype "passive"))
      (node (ref "C2") (pin "1") (pinfunction "-_1") (pintype "passive"))
      (node (ref "C20") (pin "2") (pinfunction "2_2") (pintype "passive"))
      (node (ref "C22") (pin "2") (pinfunction "2_2") (pintype "passive"))
      (node (ref "C24") (pin "2") (pinfunction "2_2") (pintype "passive"))
      (node (ref "C25") (pin "2") (pinfunction "2_2") (pintype "passive"))
      (node (ref "C26") (pin "1") (pinfunction "1_1") (pintype "passive"))
      (node (ref "C27") (pin "1") (pinfunction "1_1") (pintype "passive"))
      (node (ref "C28") (pin "-") (pinfunction "-_-") (pintype "passive"))
      (node (ref "C29") (pin "-") (pinfunction "-_-") (pintype "passive"))
      (node (ref "C3") (pin "2") (pinfunction "2_2") (pintype "passive"))
      (node (ref "C4") (pin "2") (pinfunction "2_2") (pintype "passive"))
      (node (ref "C5") (pin "2") (pinfunction "2_2") (pintype "passive"))
      (node (ref "C7") (pin "2") (pinfunction "2_2") (pintype "passive"))
      (node (ref "C8") (pin "2") (pinfunction "2_2") (pintype "passive"))
      (node (ref "C9") (pin "2") (pinfunction "2_2") (pintype "passive"))
      (node (ref "IC1") (pin "10") (pinfunction "GND_10") (pintype "power_in"))
      (node (ref "IC1") (pin "2") (pinfunction "GND_2") (pintype "power_in"))
      (node (ref "IC2") (pin "12") (pinfunction "GND_12") (pintype "power_in"))
      (node (ref "IC3") (pin "P23") (pinfunction "GND(2)_P23") (pintype "bidirectional"))
      (node (ref "IC3") (pin "P33") (pinfunction "GND(1)_P33") (pintype "bidirectional"))
      (node (ref "IC3") (pin "P45") (pinfunction "AGND_P45") (pintype "bidirectional"))
      (node (ref "IC3") (pin "P9") (pinfunction "GND(3)_P9") (pintype "bidirectional"))
      (node (ref "J1") (pin "P$4") (pinfunction "P$4_P$4") (pintype "bidirectional"))
      (node (ref "J7") (pin "4") (pinfunction "P$4_4") (pintype "bidirectional"))
      (node (ref "J9") (pin "P2") (pinfunction "P2_P2") (pintype "bidirectional"))
      (node (ref "LED1") (pin "C") (pinfunction "C_C") (pintype "passive"))
      (node (ref "LED2") (pin "C") (pinfunction "C_C") (pintype "passive"))
      (node (ref "LED3") (pin "C") (pinfunction "C_C") (pintype "passive"))
      (node (ref "R12") (pin "2") (pinfunction "2_2") (pintype "passive"))
      (node (ref "R23") (pin "1") (pinfunction "1_1") (pintype "passive"))
      (node (ref "R52") (pin "1") (pinfunction "1_1") (pintype "passive"))
      (node (ref "R53") (pin "1") (pinfunction "1_1") (pintype "passive"))
      (node (ref "S1") (pin "P$1") (pinfunction "P1_P$1") (pintype "bidirectional"))
      (node (ref "S2") (pin "P$2") (pinfunction "P2_P$2") (pintype "bidirectional"))
      (node (ref "S2") (pin "P$4") (pinfunction "P4_P$4") (pintype "bidirectional"))
      (node (ref "SEND") (pin "C") (pinfunction "C_C") (pintype "passive"))
      (node (ref "SV1") (pin "1") (pinfunction "1_1") (pintype "passive"))
      (node (ref "T11") (pin "2") (pinfunction "S_2") (pintype "passive"))
      (node (ref "T12") (pin "P$1") (pinfunction "S1_P$1") (pintype "bidirectional"))
      (node (ref "T12") (pin "P$2") (pinfunction "S2_P$2") (pintype "bidirectional"))
      (node (ref "T12") (pin "P$3") (pinfunction "S3_P$3") (pintype "bidirectional"))
      (node (ref "T13") (pin "P$1") (pinfunction "S1_P$1") (pintype "bidirectional"))
      (node (ref "T13") (pin "P$2") (pinfunction "S2_P$2") (pintype "bidirectional"))
      (node (ref "T13") (pin "P$3") (pinfunction "S3_P$3") (pintype "bidirectional"))
      (node (ref "T5") (pin "P$1") (pinfunction "S1_P$1") (pintype "bidirectional"))
      (node (ref "T5") (pin "P$2") (pinfunction "S2_P$2") (pintype "bidirectional"))
      (node (ref "T5") (pin "P$3") (pinfunction "S3_P$3") (pintype "bidirectional"))
      (node (ref "T6") (pin "P$1") (pinfunction "S1_P$1") (pintype "bidirectional"))
      (node (ref "T6") (pin "P$2") (pinfunction "S2_P$2") (pintype "bidirectional"))
      (node (ref "T6") (pin "P$3") (pinfunction "S3_P$3") (pintype "bidirectional"))
      (node (ref "U$10") (pin "GND") (pinfunction "GND_GND") (pintype "bidirectional"))
      (node (ref "U$12") (pin "P$2") (pinfunction "P2_P$2") (pintype "bidirectional"))
      (node (ref "U$16") (pin "GND") (pinfunction "GND_GND") (pintype "bidirectional"))
      (node (ref "U$17") (pin "P$10") (pinfunction "GND2_P$10") (pintype "bidirectional"))
      (node (ref "U$17") (pin "P$7") (pinfunction "GND_P$7") (pintype "bidirectional"))
      (node (ref "U$2") (pin "P$1") (pinfunction "P$1_P$1") (pintype "bidirectional"))
      (node (ref "U$8") (pin "GND") (pinfunction "GND_GND") (pintype "bidirectional"))
      (node (ref "U2") (pin "P$10") (pinfunction "P$2_P$10") (pintype "bidirectional"))
      (node (ref "U2") (pin "P$11") (pinfunction "P$2_P$11") (pintype "bidirectional"))
      (node (ref "U2") (pin "P$12") (pinfunction "P$2_P$12") (pintype "bidirectional"))
      (node (ref "U2") (pin "P$13") (pinfunction "P$2_P$13") (pintype "bidirectional"))
      (node (ref "U2") (pin "P$6") (pinfunction "GND_P$6") (pintype "bidirectional"))
      (node (ref "U2") (pin "P$9") (pinfunction "PGND_P$9") (pintype "bidirectional"))
      (node (ref "U3") (pin "P$21") (pinfunction "AGND_P$21") (pintype "bidirectional"))
      (node (ref "U3") (pin "P$3") (pinfunction "GND_P$3") (pintype "bidirectional"))
      (node (ref "U3") (pin "P$5") (pinfunction "GND2_P$5") (pintype "bidirectional"))
      (node (ref "U4") (pin "P$3") (pinfunction "GND_P$3") (pintype "bidirectional"))
      (node (ref "U4") (pin "P$4") (pinfunction "/EN_P$4") (pintype "bidirectional"))
    )
    (net (code "10") (name "INT0") (class "Default")
      (node (ref "U$17") (pin "P$2") (pinfunction "IRQ_P$2") (pintype "bidirectional"))
      (node (ref "U3") (pin "P$32") (pinfunction "(INT0)PD2_P$32") (pintype "bidirectional"))
    )
    (net (code "11") (name "LED1") (class "Default")
      (node (ref "R48") (pin "2") (pinfunction "2_2") (pintype "passive"))
      (node (ref "U3") (pin "P$13") (pinfunction "(OC1)PB1_P$13") (pintype "bidirectional"))
    )
    (net (code "12") (name "LED2") (class "Default")
      (node (ref "R47") (pin "2") (pinfunction "2_2") (pintype "passive"))
      (node (ref "U3") (pin "P$12") (pinfunction "(ICP)PB0_P$12") (pintype "bidirectional"))
    )
    (net (code "13") (name "LED3") (class "Default")
      (node (ref "R44") (pin "2") (pinfunction "2_2") (pintype "passive"))
      (node (ref "U3") (pin "P$2") (pinfunction "(T0)PD4_P$2") (pintype "bidirectional"))
    )
    (net (code "14") (name "MISO") (class "Default")
      (node (ref "J1") (pin "P$1") (pinfunction "P$1_P$1") (pintype "bidirectional"))
      (node (ref "U$17") (pin "P$1") (pinfunction "SDO_P$1") (pintype "bidirectional"))
      (node (ref "U3") (pin "P$16") (pinfunction "(MISO)PB4_P$16") (pintype "bidirectional"))
    )
    (net (code "15") (name "MOSI") (class "Default")
      (node (ref "J1") (pin "P$5") (pinfunction "P$5_P$5") (pintype "bidirectional"))
      (node (ref "U$17") (pin "P$12") (pinfunction "SDI_P$12") (pintype "bidirectional"))
      (node (ref "U3") (pin "P$15") (pinfunction "(MOSI)PB3_P$15") (pintype "bidirectional"))
    )
    (net (code "16") (name "MOTOR1_NEG") (class "Default")
      (node (ref "J2") (pin "GND") (pinfunction "P$2_GND") (pintype "bidirectional"))
      (node (ref "R24") (pin "1") (pinfunction "1_1") (pintype "passive"))
      (node (ref "T5") (pin "P$5") (pinfunction "D1_P$5") (pintype "bidirectional"))
      (node (ref "T5") (pin "P$6") (pinfunction "D2_P$6") (pintype "bidirectional"))
      (node (ref "T5") (pin "P$7") (pinfunction "D3_P$7") (pintype "bidirectional"))
      (node (ref "T5") (pin "P$8") (pinfunction "D4_P$8") (pintype "bidirectional"))
      (node (ref "U$3") (pin "P$1") (pinfunction "P$1_P$1") (pintype "bidirectional"))
    )
    (net (code "17") (name "MOTOR1_PWM_1V8") (class "Default")
      (node (ref "IC3") (pin "P38") (pinfunction "GPIO144/PWM9_P38") (pintype "bidirectional"))
      (node (ref "R13") (pin "1") (pinfunction "1_1") (pintype "passive"))
      (node (ref "T7") (pin "2") (pinfunction "S_2") (pintype "passive"))
    )
    (net (code "18") (name "MOTOR1_PWM_5V") (class "Default")
      (node (ref "R14") (pin "1") (pinfunction "1_1") (pintype "passive"))
      (node (ref "SJ1") (pin "2") (pinfunction "2_2") (pintype "passive"))
      (node (ref "T7") (pin "1") (pinfunction "D_1") (pintype "passive"))
    )
    (net (code "19") (name "MOTOR1_RPM") (class "Default")
      (node (ref "IC2") (pin "13") (pinfunction "OUT_13") (pintype "open_collector"))
      (node (ref "U3") (pin "P$10") (pinfunction "(AIN0)PD6_P$10") (pintype "bidirectional"))
    )
    (net (code "20") (name "MOTOR1_SENSE") (class "Default")
      (node (ref "R29") (pin "1") (pinfunction "1_1") (pintype "passive"))
      (node (ref "U$15") (pin "SIGNAL") (pinfunction "P$1_SIGNAL") (pintype "bidirectional"))
    )
    (net (code "21") (name "MOTOR2_NEG") (class "Default")
      (node (ref "J5") (pin "GND") (pinfunction "P$2_GND") (pintype "bidirectional"))
      (node (ref "R27") (pin "1") (pinfunction "1_1") (pintype "passive"))
      (node (ref "T13") (pin "P$5") (pinfunction "D1_P$5") (pintype "bidirectional"))
      (node (ref "T13") (pin "P$6") (pinfunction "D2_P$6") (pintype "bidirectional"))
      (node (ref "T13") (pin "P$7") (pinfunction "D3_P$7") (pintype "bidirectional"))
      (node (ref "T13") (pin "P$8") (pinfunction "D4_P$8") (pintype "bidirectional"))
      (node (ref "U$6") (pin "P$1") (pinfunction "P$1_P$1") (pintype "bidirectional"))
    )
    (net (code "22") (name "MOTOR2_PWM_1V8") (class "Default")
      (node (ref "IC3") (pin "P36") (pinfunction "GPIO145/PWM10_P36") (pintype "bidirectional"))
      (node (ref "R15") (pin "1") (pinfunction "1_1") (pintype "passive"))
      (node (ref "T8") (pin "2") (pinfunction "S_2") (pintype "passive"))
    )
    (net (code "23") (name "MOTOR2_PWM_5V") (class "Default")
      (node (ref "R16") (pin "1") (pinfunction "1_1") (pintype "passive"))
      (node (ref "SJ4") (pin "2") (pinfunction "2_2") (pintype "passive"))
      (node (ref "T8") (pin "1") (pinfunction "D_1") (pintype "passive"))
    )
    (net (code "24") (name "MOTOR2_RPM") (class "Default")
      (node (ref "IC2") (pin "14") (pinfunction "OUT_14") (pintype "open_collector"))
      (node (ref "U3") (pin "P$9") (pinfunction "(T1)PD5_P$9") (pintype "bidirectional"))
    )
    (net (code "25") (name "MOTOR2_SENSE") (class "Default")
      (node (ref "R31") (pin "1") (pinfunction "1_1") (pintype "passive"))
      (node (ref "U$14") (pin "SIGNAL") (pinfunction "P$1_SIGNAL") (pintype "bidirectional"))
    )
    (net (code "26") (name "MOTOR3_NEG") (class "Default")
      (node (ref "J3") (pin "GND") (pinfunction "P$2_GND") (pintype "bidirectional"))
      (node (ref "R26") (pin "1") (pinfunction "1_1") (pintype "passive"))
      (node (ref "T12") (pin "P$5") (pinfunction "D1_P$5") (pintype "bidirectional"))
      (node (ref "T12") (pin "P$6") (pinfunction "D2_P$6") (pintype "bidirectional"))
      (node (ref "T12") (pin "P$7") (pinfunction "D3_P$7") (pintype "bidirectional"))
      (node (ref "T12") (pin "P$8") (pinfunction "D4_P$8") (pintype "bidirectional"))
      (node (ref "U$5") (pin "P$1") (pinfunction "P$1_P$1") (pintype "bidirectional"))
    )
    (net (code "27") (name "MOTOR3_PWM_1V8") (class "Default")
      (node (ref "IC3") (pin "P35") (pinfunction "GPIO146/PWM11_P35") (pintype "bidirectional"))
      (node (ref "R17") (pin "1") (pinfunction "1_1") (pintype "passive"))
      (node (ref "T9") (pin "2") (pinfunction "S_2") (pintype "passive"))
    )
    (net (code "28") (name "MOTOR3_PWM_5V") (class "Default")
      (node (ref "R18") (pin "1") (pinfunction "1_1") (pintype "passive"))
      (node (ref "SJ3") (pin "2") (pinfunction "2_2") (pintype "passive"))
      (node (ref "T9") (pin "1") (pinfunction "D_1") (pintype "passive"))
    )
    (net (code "29") (name "MOTOR3_RPM") (class "Default")
      (node (ref "IC2") (pin "1") (pinfunction "OUT_1") (pintype "open_collector"))
      (node (ref "U3") (pin "P$31") (pinfunction "(TXD)PD1_P$31") (pintype "bidirectional"))
    )
    (net (code "30") (name "MOTOR3_SENSE") (class "Default")
      (node (ref "R33") (pin "1") (pinfunction "1_1") (pintype "passive"))
      (node (ref "U$11") (pin "SIGNAL") (pinfunction "P$1_SIGNAL") (pintype "bidirectional"))
    )
    (net (code "31") (name "MOTOR4_NEG") (class "Default")
      (node (ref "J4") (pin "GND") (pinfunction "P$2_GND") (pintype "bidirectional"))
      (node (ref "R25") (pin "1") (pinfunction "1_1") (pintype "passive"))
      (node (ref "T6") (pin "P$5") (pinfunction "D1_P$5") (pintype "bidirectional"))
      (node (ref "T6") (pin "P$6") (pinfunction "D2_P$6") (pintype "bidirectional"))
      (node (ref "T6") (pin "P$7") (pinfunction "D3_P$7") (pintype "bidirectional"))
      (node (ref "T6") (pin "P$8") (pinfunction "D4_P$8") (pintype "bidirectional"))
      (node (ref "U$4") (pin "P$1") (pinfunction "P$1_P$1") (pintype "bidirectional"))
    )
    (net (code "32") (name "MOTOR4_PWM_1V8") (class "Default")
      (node (ref "IC3") (pin "P37") (pinfunction "GPIO147/PWM8_P37") (pintype "bidirectional"))
      (node (ref "R19") (pin "1") (pinfunction "1_1") (pintype "passive"))
      (node (ref "T10") (pin "2") (pinfunction "S_2") (pintype "passive"))
    )
    (net (code "33") (name "MOTOR4_PWM_5V") (class "Default")
      (node (ref "R20") (pin "1") (pinfunction "1_1") (pintype "passive"))
      (node (ref "SJ2") (pin "2") (pinfunction "2_2") (pintype "passive"))
      (node (ref "T10") (pin "1") (pinfunction "D_1") (pintype "passive"))
    )
    (net (code "34") (name "MOTOR4_RPM") (class "Default")
      (node (ref "IC2") (pin "2") (pinfunction "OUT_2") (pintype "open_collector"))
      (node (ref "U3") (pin "P$30") (pinfunction "(RXD)PD0_P$30") (pintype "bidirectional"))
    )
    (net (code "35") (name "MOTOR4_SENSE") (class "Default")
      (node (ref "R35") (pin "1") (pinfunction "1_1") (pintype "passive"))
      (node (ref "U$9") (pin "SIGNAL") (pinfunction "P$1_SIGNAL") (pintype "bidirectional"))
    )
    (net (code "36") (name "MOTOR_ENABLE") (class "Default")
      (node (ref "MR1") (pin "1") (pinfunction "D_1") (pintype "passive"))
      (node (ref "R23") (pin "2") (pinfunction "2_2") (pintype "passive"))
      (node (ref "T12") (pin "P$4") (pinfunction "G_P$4") (pintype "bidirectional"))
      (node (ref "T13") (pin "P$4") (pinfunction "G_P$4") (pintype "bidirectional"))
      (node (ref "T5") (pin "P$4") (pinfunction "G_P$4") (pintype "bidirectional"))
      (node (ref "T6") (pin "P$4") (pinfunction "G_P$4") (pintype "bidirectional"))
    )
    (net (code "37") (name "MOTOR_LOGIC") (class "Default")
      (node (ref "T11") (pin "3") (pinfunction "G_3") (pintype "passive"))
      (node (ref "U3") (pin "P$11") (pinfunction "(AIN1)PD7_P$11") (pintype "bidirectional"))
    )
    (net (code "38") (name "N$37") (class "Default")
      (node (ref "J9") (pin "P1") (pinfunction "P1_P1") (pintype "bidirectional"))
      (node (ref "Q2") (pin "5") (pinfunction "D_5") (pintype "passive"))
      (node (ref "Q2") (pin "6") (pinfunction "D_6") (pintype "passive"))
      (node (ref "Q2") (pin "7") (pinfunction "D_7") (pintype "passive"))
      (node (ref "Q2") (pin "8") (pinfunction "D_8") (pintype "passive"))
    )
    (net (code "39") (name "Net-(C17-Pad1)") (class "Default")
      (node (ref "C17") (pin "1") (pinfunction "1_1") (pintype "passive"))
      (node (ref "C18") (pin "1") (pinfunction "1_1") (pintype "passive"))
      (node (ref "R29") (pin "2") (pinfunction "2_2") (pintype "passive"))
    )
    (net (code "40") (name "Net-(C19-Pad1)") (class "Default")
      (node (ref "C19") (pin "1") (pinfunction "1_1") (pintype "passive"))
      (node (ref "C20") (pin "1") (pinfunction "1_1") (pintype "passive"))
      (node (ref "R31") (pin "2") (pinfunction "2_2") (pintype "passive"))
    )
    (net (code "41") (name "Net-(C21-Pad1)") (class "Default")
      (node (ref "C21") (pin "1") (pinfunction "1_1") (pintype "passive"))
      (node (ref "C22") (pin "1") (pinfunction "1_1") (pintype "passive"))
      (node (ref "R33") (pin "2") (pinfunction "2_2") (pintype "passive"))
    )
    (net (code "42") (name "Net-(C23-Pad1)") (class "Default")
      (node (ref "C23") (pin "1") (pinfunction "1_1") (pintype "passive"))
      (node (ref "C24") (pin "1") (pinfunction "1_1") (pintype "passive"))
      (node (ref "R35") (pin "2") (pinfunction "2_2") (pintype "passive"))
    )
    (net (code "43") (name "Net-(IC1-AREF)") (class "Default")
      (node (ref "IC1") (pin "5") (pinfunction "AREF_5") (pintype "passive"))
      (node (ref "R45") (pin "2") (pinfunction "2_2") (pintype "passive"))
    )
    (net (code "44") (name "Net-(IC1-LADJ)") (class "Default")
      (node (ref "IC1") (pin "12") (pinfunction "LADJ_12") (pintype "power_in"))
      (node (ref "R46") (pin "1") (pinfunction "1_1") (pintype "passive"))
    )
    (net (code "45") (name "Net-(IC2A--IN)") (class "Default")
      (node (ref "C17") (pin "2") (pinfunction "2_2") (pintype "passive"))
      (node (ref "IC2") (pin "4") (pinfunction "-IN_4") (pintype "input"))
      (node (ref "R28") (pin "2") (pinfunction "2_2") (pintype "passive"))
    )
    (net (code "46") (name "Net-(IC2B--IN)") (class "Default")
      (node (ref "C19") (pin "2") (pinfunction "2_2") (pintype "passive"))
      (node (ref "IC2") (pin "6") (pinfunction "-IN_6") (pintype "input"))
      (node (ref "R30") (pin "2") (pinfunction "2_2") (pintype "passive"))
    )
    (net (code "47") (name "Net-(IC2C--IN)") (class "Default")
      (node (ref "C21") (pin "2") (pinfunction "2_2") (pintype "passive"))
      (node (ref "IC2") (pin "8") (pinfunction "-IN_8") (pintype "input"))
      (node (ref "R32") (pin "2") (pinfunction "2_2") (pintype "passive"))
    )
    (net (code "48") (name "Net-(IC2D--IN)") (class "Default")
      (node (ref "C23") (pin "2") (pinfunction "2_2") (pintype "passive"))
      (node (ref "IC2") (pin "10") (pinfunction "-IN_10") (pintype "input"))
      (node (ref "R34") (pin "2") (pinfunction "2_2") (pintype "passive"))
    )
    (net (code "49") (name "Net-(J2-P$3)") (class "Default")
      (node (ref "J2") (pin "SIG") (pinfunction "P$3_SIG") (pintype "bidirectional"))
      (node (ref "SJ1") (pin "1") (pinfunction "1_1") (pintype "passive"))
    )
    (net (code "50") (name "Net-(J3-P$3)") (class "Default")
      (node (ref "J3") (pin "SIG") (pinfunction "P$3_SIG") (pintype "bidirectional"))
      (node (ref "SJ3") (pin "1") (pinfunction "1_1") (pintype "passive"))
    )
    (net (code "51") (name "Net-(J4-P$3)") (class "Default")
      (node (ref "J4") (pin "SIG") (pinfunction "P$3_SIG") (pintype "bidirectional"))
      (node (ref "SJ2") (pin "1") (pinfunction "1_1") (pintype "passive"))
    )
    (net (code "52") (name "Net-(J5-P$3)") (class "Default")
      (node (ref "J5") (pin "SIG") (pinfunction "P$3_SIG") (pintype "bidirectional"))
      (node (ref "SJ4") (pin "1") (pinfunction "1_1") (pintype "passive"))
    )
    (net (code "53") (name "Net-(LED1-PadA)") (class "Default")
      (node (ref "LED1") (pin "A") (pinfunction "A_A") (pintype "passive"))
      (node (ref "R44") (pin "1") (pinfunction "1_1") (pintype "passive"))
    )
    (net (code "54") (name "Net-(LED2-PadA)") (class "Default")
      (node (ref "LED2") (pin "A") (pinfunction "A_A") (pintype "passive"))
      (node (ref "R47") (pin "1") (pinfunction "1_1") (pintype "passive"))
    )
    (net (code "55") (name "Net-(LED3-PadA)") (class "Default")
      (node (ref "LED3") (pin "A") (pinfunction "A_A") (pintype "passive"))
      (node (ref "R48") (pin "1") (pinfunction "1_1") (pintype "passive"))
    )
    (net (code "56") (name "Net-(MOTOR1-PadC)") (class "Default")
      (node (ref "MOTOR1") (pin "C") (pinfunction "C_C") (pintype "passive"))
      (node (ref "R24") (pin "2") (pinfunction "2_2") (pintype "passive"))
    )
    (net (code "57") (name "Net-(MOTOR2-PadC)") (class "Default")
      (node (ref "MOTOR2") (pin "C") (pinfunction "C_C") (pintype "passive"))
      (node (ref "R25") (pin "2") (pinfunction "2_2") (pintype "passive"))
    )
    (net (code "58") (name "Net-(MOTOR3-PadC)") (class "Default")
      (node (ref "MOTOR3") (pin "C") (pinfunction "C_C") (pintype "passive"))
      (node (ref "R26") (pin "2") (pinfunction "2_2") (pintype "passive"))
    )
    (net (code "59") (name "Net-(MOTOR4-PadC)") (class "Default")
      (node (ref "MOTOR4") (pin "C") (pinfunction "C_C") (pintype "passive"))
      (node (ref "R27") (pin "2") (pinfunction "2_2") (pintype "passive"))
    )
    (net (code "60") (name "Net-(MR1-G)") (class "Default")
      (node (ref "MR1") (pin "3") (pinfunction "G_3") (pintype "passive"))
      (node (ref "R8") (pin "1") (pinfunction "1_1") (pintype "passive"))
      (node (ref "T11") (pin "1") (pinfunction "D_1") (pintype "passive"))
    )
    (net (code "61") (name "Net-(R49-Pad1)") (class "Default")
      (node (ref "R49") (pin "1") (pinfunction "1_1") (pintype "passive"))
      (node (ref "SEND") (pin "A") (pinfunction "A_A") (pintype "passive"))
    )
    (net (code "62") (name "Net-(R50-Pad2)") (class "Default")
      (node (ref "R50") (pin "2") (pinfunction "2_2") (pintype "passive"))
      (node (ref "RECEIVE") (pin "C") (pinfunction "C_C") (pintype "passive"))
    )
    (net (code "63") (name "Net-(U$1-1)") (class "Default")
      (node (ref "C6") (pin "2") (pinfunction "2_2") (pintype "passive"))
      (node (ref "U$1") (pin "P1") (pinfunction "1_P1") (pintype "bidirectional"))
      (node (ref "U$2") (pin "P$2") (pinfunction "P$2_P$2") (pintype "bidirectional"))
      (node (ref "U2") (pin "P$8") (pinfunction "PH_P$8") (pintype "bidirectional"))
    )
    (net (code "64") (name "Net-(U$17-FFS)") (class "Default")
      (node (ref "R21") (pin "2") (pinfunction "2_2") (pintype "passive"))
      (node (ref "U$17") (pin "P$3") (pinfunction "FFS_P$3") (pintype "bidirectional"))
    )
    (net (code "65") (name "Net-(U2A-BOOT)") (class "Default")
      (node (ref "C6") (pin "1") (pinfunction "1_1") (pintype "passive"))
      (node (ref "U2") (pin "P$1") (pinfunction "BOOT_P$1") (pintype "bidirectional"))
    )
    (net (code "66") (name "Net-(U2A-ENA)") (class "Default")
      (node (ref "R22") (pin "2") (pinfunction "2_2") (pintype "passive"))
      (node (ref "R53") (pin "2") (pinfunction "2_2") (pintype "passive"))
      (node (ref "U2") (pin "P$5") (pinfunction "ENA_P$5") (pintype "bidirectional"))
    )
    (net (code "67") (name "Net-(U2A-VSNS)") (class "Default")
      (node (ref "R11") (pin "1") (pinfunction "1_1") (pintype "passive"))
      (node (ref "R12") (pin "1") (pinfunction "1_1") (pintype "passive"))
      (node (ref "U2") (pin "P$4") (pinfunction "VSNS_P$4") (pintype "bidirectional"))
    )
    (net (code "68") (name "Net-(U3-AREF)") (class "Default")
      (node (ref "C12") (pin "1") (pinfunction "1_1") (pintype "passive"))
      (node (ref "U3") (pin "P$20") (pinfunction "AREF_P$20") (pintype "bidirectional"))
    )
    (net (code "69") (name "Net-(U3-XTAL1)") (class "Default")
      (node (ref "C15") (pin "2") (pinfunction "2_2") (pintype "passive"))
      (node (ref "Q1") (pin "P$1") (pinfunction "P$1_P$1") (pintype "bidirectional"))
      (node (ref "U3") (pin "P$7") (pinfunction "XTAL1_P$7") (pintype "bidirectional"))
    )
    (net (code "70") (name "Net-(U3-XTAL2)") (class "Default")
      (node (ref "C14") (pin "2") (pinfunction "2_2") (pintype "passive"))
      (node (ref "Q1") (pin "P$2") (pinfunction "P$2_P$2") (pintype "bidirectional"))
      (node (ref "U3") (pin "P$8") (pinfunction "XTAL2_P$8") (pintype "bidirectional"))
    )
    (net (code "71") (name "OPT_SIG") (class "Default")
      (node (ref "U$16") (pin "SIG") (pinfunction "SIG_SIG") (pintype "bidirectional"))
      (node (ref "U3") (pin "P$23") (pinfunction "(ADC0)PC0_P$23") (pintype "bidirectional"))
    )
    (net (code "72") (name "PING0") (class "Default")
      (node (ref "U$10") (pin "SIG") (pinfunction "SIG_SIG") (pintype "bidirectional"))
      (node (ref "U3") (pin "P$1") (pinfunction "(INT1)PD3_P$1") (pintype "bidirectional"))
    )
    (net (code "73") (name "RESET") (class "Default")
      (node (ref "J1") (pin "P$3") (pinfunction "P$3_P$3") (pintype "bidirectional"))
      (node (ref "R7") (pin "1") (pinfunction "1_1") (pintype "passive"))
      (node (ref "S2") (pin "P$1") (pinfunction "P1_P$1") (pintype "bidirectional"))
      (node (ref "S2") (pin "P$3") (pinfunction "P3_P$3") (pintype "bidirectional"))
      (node (ref "U3") (pin "P$29") (pinfunction "RESET_P$29") (pintype "bidirectional"))
    )
    (net (code "74") (name "RF_SEL_3V") (class "Default")
      (node (ref "IC1") (pin "8") (pinfunction "TR_SEL_8") (pintype "input"))
      (node (ref "R3") (pin "1") (pinfunction "1_1") (pintype "passive"))
      (node (ref "T1") (pin "2") (pinfunction "S_2") (pintype "passive"))
    )
    (net (code "75") (name "RF_SEL_5V") (class "Default")
      (node (ref "R49") (pin "2") (pinfunction "2_2") (pintype "passive"))
      (node (ref "R50") (pin "1") (pinfunction "1_1") (pintype "passive"))
      (node (ref "R6") (pin "1") (pinfunction "1_1") (pintype "passive"))
      (node (ref "T1") (pin "1") (pinfunction "D_1") (pintype "passive"))
      (node (ref "U$17") (pin "P$14") (pinfunction "SEL_P$14") (pintype "bidirectional"))
      (node (ref "U3") (pin "P$14") (pinfunction "(SS)PB2_P$14") (pintype "bidirectional"))
    )
    (net (code "76") (name "RSSI") (class "Default")
      (node (ref "IC1") (pin "4") (pinfunction "RSSI_4") (pintype "passive"))
      (node (ref "U3") (pin "P$26") (pinfunction "(ADC3)PC3_P$26") (pintype "bidirectional"))
    )
    (net (code "77") (name "RXD1") (class "Default")
      (node (ref "IC3") (pin "P17") (pinfunction "GPIO151/RXD1_P17") (pintype "bidirectional"))
      (node (ref "J7") (pin "3") (pinfunction "P$3_3") (pintype "bidirectional"))
    )
    (net (code "78") (name "SCK") (class "Default")
      (node (ref "J1") (pin "P$2") (pinfunction "P$2_P$2") (pintype "bidirectional"))
      (node (ref "U$17") (pin "P$13") (pinfunction "SCK_P$13") (pintype "bidirectional"))
      (node (ref "U3") (pin "P$17") (pinfunction "(SCK)PB5_P$17") (pintype "bidirectional"))
    )
    (net (code "79") (name "SCL_1V8") (class "Default")
      (node (ref "IC3") (pin "P31") (pinfunction "GPIO184/SCL_P31") (pintype "bidirectional"))
      (node (ref "R1") (pin "1") (pinfunction "1_1") (pintype "passive"))
      (node (ref "T3") (pin "2") (pinfunction "S_2") (pintype "passive"))
    )
    (net (code "80") (name "SCL_5V") (class "Default")
      (node (ref "R2") (pin "1") (pinfunction "1_1") (pintype "passive"))
      (node (ref "SV1") (pin "4") (pinfunction "4_4") (pintype "passive"))
      (node (ref "T3") (pin "1") (pinfunction "D_1") (pintype "passive"))
      (node (ref "U3") (pin "P$28") (pinfunction "(ADC5)PC5_P$28") (pintype "bidirectional"))
    )
    (net (code "81") (name "SDA_1V8") (class "Default")
      (node (ref "IC3") (pin "P32") (pinfunction "GPIO185/SDA_P32") (pintype "bidirectional"))
      (node (ref "R9") (pin "1") (pinfunction "1_1") (pintype "passive"))
      (node (ref "T4") (pin "2") (pinfunction "S_2") (pintype "passive"))
    )
    (net (code "82") (name "SDA_5V") (class "Default")
      (node (ref "R10") (pin "1") (pinfunction "1_1") (pintype "passive"))
      (node (ref "SV1") (pin "3") (pinfunction "3_3") (pintype "passive"))
      (node (ref "T4") (pin "1") (pinfunction "D_1") (pintype "passive"))
      (node (ref "U3") (pin "P$27") (pinfunction "(ADC4)PC4_P$27") (pintype "bidirectional"))
    )
    (net (code "83") (name "TXD1") (class "Default")
      (node (ref "IC3") (pin "P18") (pinfunction "GPIO148/TXD1_P18") (pintype "bidirectional"))
      (node (ref "J7") (pin "2") (pinfunction "P$2_2") (pintype "bidirectional"))
    )
    (net (code "84") (name "VCC") (class "Default")
      (node (ref "C1") (pin "1") (pinfunction "1_1") (pintype "passive"))
      (node (ref "C8") (pin "1") (pinfunction "1_1") (pintype "passive"))
      (node (ref "IC1") (pin "11") (pinfunction "VCC_11") (pintype "power_in"))
      (node (ref "IC1") (pin "9") (pinfunction "PDN_9") (pintype "input"))
      (node (ref "R3") (pin "2") (pinfunction "2_2") (pintype "passive"))
      (node (ref "R4") (pin "2") (pinfunction "2_2") (pintype "passive"))
      (node (ref "R45") (pin "1") (pinfunction "1_1") (pintype "passive"))
      (node (ref "R46") (pin "2") (pinfunction "2_2") (pintype "passive"))
      (node (ref "T1") (pin "3") (pinfunction "G_3") (pintype "passive"))
      (node (ref "T2") (pin "3") (pinfunction "G_3") (pintype "passive"))
      (node (ref "U4") (pin "P$7") (pinfunction "OUT_P$7") (pintype "bidirectional"))
      (node (ref "U4") (pin "P$8") (pinfunction "OUT2_P$8") (pintype "bidirectional"))
    )
    (net (code "85") (name "unconnected-(IC1-ANALOG-Pad6)") (class "Default")
      (node (ref "IC1") (pin "6") (pinfunction "ANALOG_6") (pintype "output"))
    )
    (net (code "86") (name "unconnected-(IC1-NC-Pad3)") (class "Default")
      (node (ref "IC1") (pin "3") (pinfunction "NC_3") (pintype "no_connect"))
    )
    (net (code "87") (name "unconnected-(IC3-ADCIN2-PadP42)") (class "Default")
      (node (ref "IC3") (pin "P42") (pinfunction "ADCIN2_P42") (pintype "bidirectional"))
    )
    (net (code "88") (name "unconnected-(IC3-ADCIN3-PadP46)") (class "Default")
      (node (ref "IC3") (pin "P46") (pinfunction "ADCIN3_P46") (pintype "bidirectional"))
    )
    (net (code "89") (name "unconnected-(IC3-ADCIN4-PadP47)") (class "Default")
      (node (ref "IC3") (pin "P47") (pinfunction "ADCIN4_P47") (pintype "bidirectional"))
    )
    (net (code "90") (name "unconnected-(IC3-ADCIN5-PadP44)") (class "Default")
      (node (ref "IC3") (pin "P44") (pinfunction "ADCIN5_P44") (pintype "bidirectional"))
    )
    (net (code "91") (name "unconnected-(IC3-ADCIN6-PadP43)") (class "Default")
      (node (ref "IC3") (pin "P43") (pinfunction "ADCIN6_P43") (pintype "bidirectional"))
    )
    (net (code "92") (name "unconnected-(IC3-ADCIN7-PadP41)") (class "Default")
      (node (ref "IC3") (pin "P41") (pinfunction "ADCIN7_P41") (pintype "bidirectional"))
    )
    (net (code "93") (name "unconnected-(IC3-GPIO0{slash}WAKEUP-PadP21)") (class "Default")
      (node (ref "IC3") (pin "P21") (pinfunction "GPIO0/WAKEUP_P21") (pintype "bidirectional"))
    )
    (net (code "94") (name "unconnected-(IC3-GPIO10-PadP26)") (class "Default")
      (node (ref "IC3") (pin "P26") (pinfunction "GPIO10_P26") (pintype "bidirectional"))
    )
    (net (code "95") (name "unconnected-(IC3-GPIO13(1)-PadP52)") (class "Default")
      (node (ref "IC3") (pin "P52") (pinfunction "GPIO13(1)_P52") (pintype "bidirectional"))
    )
    (net (code "96") (name "unconnected-(IC3-GPIO13(2)-PadP51)") (class "Default")
      (node (ref "IC3") (pin "P51") (pinfunction "GPIO13(2)_P51") (pintype "bidirectional"))
    )
    (net (code "97") (name "unconnected-(IC3-GPIO14-PadP56)") (class "Default")
      (node (ref "IC3") (pin "P56") (pinfunction "GPIO14_P56") (pintype "bidirectional"))
    )
    (net (code "98") (name "unconnected-(IC3-GPIO17-PadP57)") (class "Default")
      (node (ref "IC3") (pin "P57") (pinfunction "GPIO17_P57") (pintype "bidirectional"))
    )
    (net (code "99") (name "unconnected-(IC3-GPIO18-PadP60)") (class "Default")
      (node (ref "IC3") (pin "P60") (pinfunction "GPIO18_P60") (pintype "bidirectional"))
    )
    (net (code "100") (name "unconnected-(IC3-GPIO19-PadP59)") (class "Default")
      (node (ref "IC3") (pin "P59") (pinfunction "GPIO19_P59") (pintype "bidirectional"))
    )
    (net (code "101") (name "unconnected-(IC3-GPIO20-PadP58)") (class "Default")
      (node (ref "IC3") (pin "P58") (pinfunction "GPIO20_P58") (pintype "bidirectional"))
    )
    (net (code "102") (name "unconnected-(IC3-GPIO21-PadP53)") (class "Default")
      (node (ref "IC3") (pin "P53") (pinfunction "GPIO21_P53") (pintype "bidirectional"))
    )
    (net (code "103") (name "unconnected-(IC3-GPIO22-PadP54)") (class "Default")
      (node (ref "IC3") (pin "P54") (pinfunction "GPIO22_P54") (pintype "bidirectional"))
    )
    (net (code "104") (name "unconnected-(IC3-GPIO23-PadP55)") (class "Default")
      (node (ref "IC3") (pin "P55") (pinfunction "GPIO23_P55") (pintype "bidirectional"))
    )
    (net (code "105") (name "unconnected-(IC3-GPIO64-PadP4)") (class "Default")
      (node (ref "IC3") (pin "P4") (pinfunction "GPIO64_P4") (pintype "bidirectional"))
    )
    (net (code "106") (name "unconnected-(IC3-GPIO65-PadP8)") (class "Default")
      (node (ref "IC3") (pin "P8") (pinfunction "GPIO65_P8") (pintype "bidirectional"))
    )
    (net (code "107") (name "unconnected-(IC3-GPIO66-PadP1)") (class "Default")
      (node (ref "IC3") (pin "P1") (pinfunction "GPIO66_P1") (pintype "bidirectional"))
    )
    (net (code "108") (name "unconnected-(IC3-GPIO67-PadP3)") (class "Default")
      (node (ref "IC3") (pin "P3") (pinfunction "GPIO67_P3") (pintype "bidirectional"))
    )
    (net (code "109") (name "unconnected-(IC3-GPIO68-PadP5)") (class "Default")
      (node (ref "IC3") (pin "P5") (pinfunction "GPIO68_P5") (pintype "bidirectional"))
    )
    (net (code "110") (name "unconnected-(IC3-GPIO69-PadP7)") (class "Default")
      (node (ref "IC3") (pin "P7") (pinfunction "GPIO69_P7") (pintype "bidirectional"))
    )
    (net (code "111") (name "unconnected-(IC3-GPIO114{slash}SPI1_NIRQ-PadP12)") (class "Default")
      (node (ref "IC3") (pin "P12") (pinfunction "GPIO114/SPI1_NIRQ_P12") (pintype "bidirectional"))
    )
    (net (code "112") (name "unconnected-(IC3-GPIO149-PadP49)") (class "Default")
      (node (ref "IC3") (pin "P49") (pinfunction "GPIO149_P49") (pintype "bidirectional"))
    )
    (net (code "113") (name "unconnected-(IC3-GPIO150-PadP50)") (class "Default")
      (node (ref "IC3") (pin "P50") (pinfunction "GPIO150_P50") (pintype "bidirectional"))
    )
    (net (code "114") (name "unconnected-(IC3-GPIO163{slash}CTS3-PadP28)") (class "Default")
      (node (ref "IC3") (pin "P28") (pinfunction "GPIO163/CTS3_P28") (pintype "bidirectional"))
    )
    (net (code "115") (name "unconnected-(IC3-GPIO165{slash}RXD3-PadP29)") (class "Default")
      (node (ref "IC3") (pin "P29") (pinfunction "GPIO165/RXD3_P29") (pintype "bidirectional"))
    )
    (net (code "116") (name "unconnected-(IC3-GPIO166{slash}TXD3-PadP30)") (class "Default")
      (node (ref "IC3") (pin "P30") (pinfunction "GPIO166/TXD3_P30") (pintype "bidirectional"))
    )
    (net (code "117") (name "unconnected-(IC3-GPIO168-PadP2)") (class "Default")
      (node (ref "IC3") (pin "P2") (pinfunction "GPIO168_P2") (pintype "bidirectional"))
    )
    (net (code "118") (name "unconnected-(IC3-GPIO170{slash}1WIRE-PadP27)") (class "Default")
      (node (ref "IC3") (pin "P27") (pinfunction "GPIO170/1WIRE_P27") (pintype "bidirectional"))
    )
    (net (code "119") (name "unconnected-(IC3-GPIO171{slash}SPI1_CLK-PadP11)") (class "Default")
      (node (ref "IC3") (pin "P11") (pinfunction "GPIO171/SPI1_CLK_P11") (pintype "bidirectional"))
    )
    (net (code "120") (name "unconnected-(IC3-GPIO172{slash}SPI1_MOSI-PadP13)") (class "Default")
      (node (ref "IC3") (pin "P13") (pinfunction "GPIO172/SPI1_MOSI_P13") (pintype "bidirectional"))
    )
    (net (code "121") (name "unconnected-(IC3-GPIO173{slash}SPI1_MISO-PadP15)") (class "Default")
      (node (ref "IC3") (pin "P15") (pinfunction "GPIO173/SPI1_MISO_P15") (pintype "bidirectional"))
    )
    (net (code "122") (name "unconnected-(IC3-GPIO174{slash}SPI1_CS0-PadP14)") (class "Default")
      (node (ref "IC3") (pin "P14") (pinfunction "GPIO174/SPI1_CS0_P14") (pintype "bidirectional"))
    )
    (net (code "123") (name "unconnected-(IC3-GPIO175{slash}SPI1_CS1-PadP16)") (class "Default")
      (node (ref "IC3") (pin "P16") (pinfunction "GPIO175/SPI1_CS1_P16") (pintype "bidirectional"))
    )
    (net (code "124") (name "unconnected-(IC3-GPIO176-PadP6)") (class "Default")
      (node (ref "IC3") (pin "P6") (pinfunction "GPIO176_P6") (pintype "bidirectional"))
    )
    (net (code "125") (name "unconnected-(IC3-GPIO186-PadP25)") (class "Default")
      (node (ref "IC3") (pin "P25") (pinfunction "GPIO186_P25") (pintype "bidirectional"))
    )
    (net (code "126") (name "unconnected-(IC3-POWERON-PadP22)") (class "Default")
      (node (ref "IC3") (pin "P22") (pinfunction "POWERON_P22") (pintype "bidirectional"))
    )
    (net (code "127") (name "unconnected-(IC3-PWM0-PadP39)") (class "Default")
      (node (ref "IC3") (pin "P39") (pinfunction "PWM0_P39") (pintype "bidirectional"))
    )
    (net (code "128") (name "unconnected-(IC3-PWM1-PadP40)") (class "Default")
      (node (ref "IC3") (pin "P40") (pinfunction "PWM1_P40") (pintype "bidirectional"))
    )
    (net (code "129") (name "unconnected-(IC3-SYS_EN-PadP19)") (class "Default")
      (node (ref "IC3") (pin "P19") (pinfunction "SYS_EN_P19") (pintype "bidirectional"))
    )
    (net (code "130") (name "unconnected-(IC3-VBACKUP-PadP20)") (class "Default")
      (node (ref "IC3") (pin "P20") (pinfunction "VBACKUP_P20") (pintype "bidirectional"))
    )
    (net (code "131") (name "unconnected-(IC3-VCC_1V8(2)-PadP24)") (class "Default")
      (node (ref "IC3") (pin "P24") (pinfunction "VCC_1V8(2)_P24") (pintype "bidirectional"))
    )
    (net (code "132") (name "unconnected-(IC3-VCC_3V3-PadP10)") (class "Default")
      (node (ref "IC3") (pin "P10") (pinfunction "VCC_3V3_P10") (pintype "bidirectional"))
    )
    (net (code "133") (name "unconnected-(U$17-CLK-PadP$5)") (class "Default")
      (node (ref "U$17") (pin "P$5") (pinfunction "CLK_P$5") (pintype "bidirectional"))
    )
    (net (code "134") (name "unconnected-(U$17-FFIT-PadP$4)") (class "Default")
      (node (ref "U$17") (pin "P$4") (pinfunction "FFIT_P$4") (pintype "bidirectional"))
    )
    (net (code "135") (name "unconnected-(U$17-NINT-PadP$11)") (class "Default")
      (node (ref "U$17") (pin "P$11") (pinfunction "NINT_P$11") (pintype "bidirectional"))
    )
    (net (code "136") (name "unconnected-(U$17-NRES-PadP$6)") (class "Default")
      (node (ref "U$17") (pin "P$6") (pinfunction "NRES_P$6") (pintype "bidirectional"))
    )
    (net (code "137") (name "unconnected-(U3-(ADC2)PC2-PadP$25)") (class "Default")
      (node (ref "U3") (pin "P$25") (pinfunction "(ADC2)PC2_P$25") (pintype "bidirectional"))
    )
    (net (code "138") (name "unconnected-(U3-ADC7-PadP$22)") (class "Default")
      (node (ref "U3") (pin "P$22") (pinfunction "ADC7_P$22") (pintype "bidirectional"))
    )
    (net (code "139") (name "unconnected-(U4-FB{slash}NC-PadP$1)") (class "Default")
      (node (ref "U4") (pin "P$1") (pinfunction "FB/NC_P$1") (pintype "bidirectional"))
    )
    (net (code "140") (name "unconnected-(U4-PG-PadP$2)") (class "Default")
      (node (ref "U4") (pin "P$2") (pinfunction "PG_P$2") (pintype "bidirectional"))
    )
  )
)
